# SCH-HC15C_REV1_PG3.net
KiCad netlist of a schematic drawn in Altium Designer
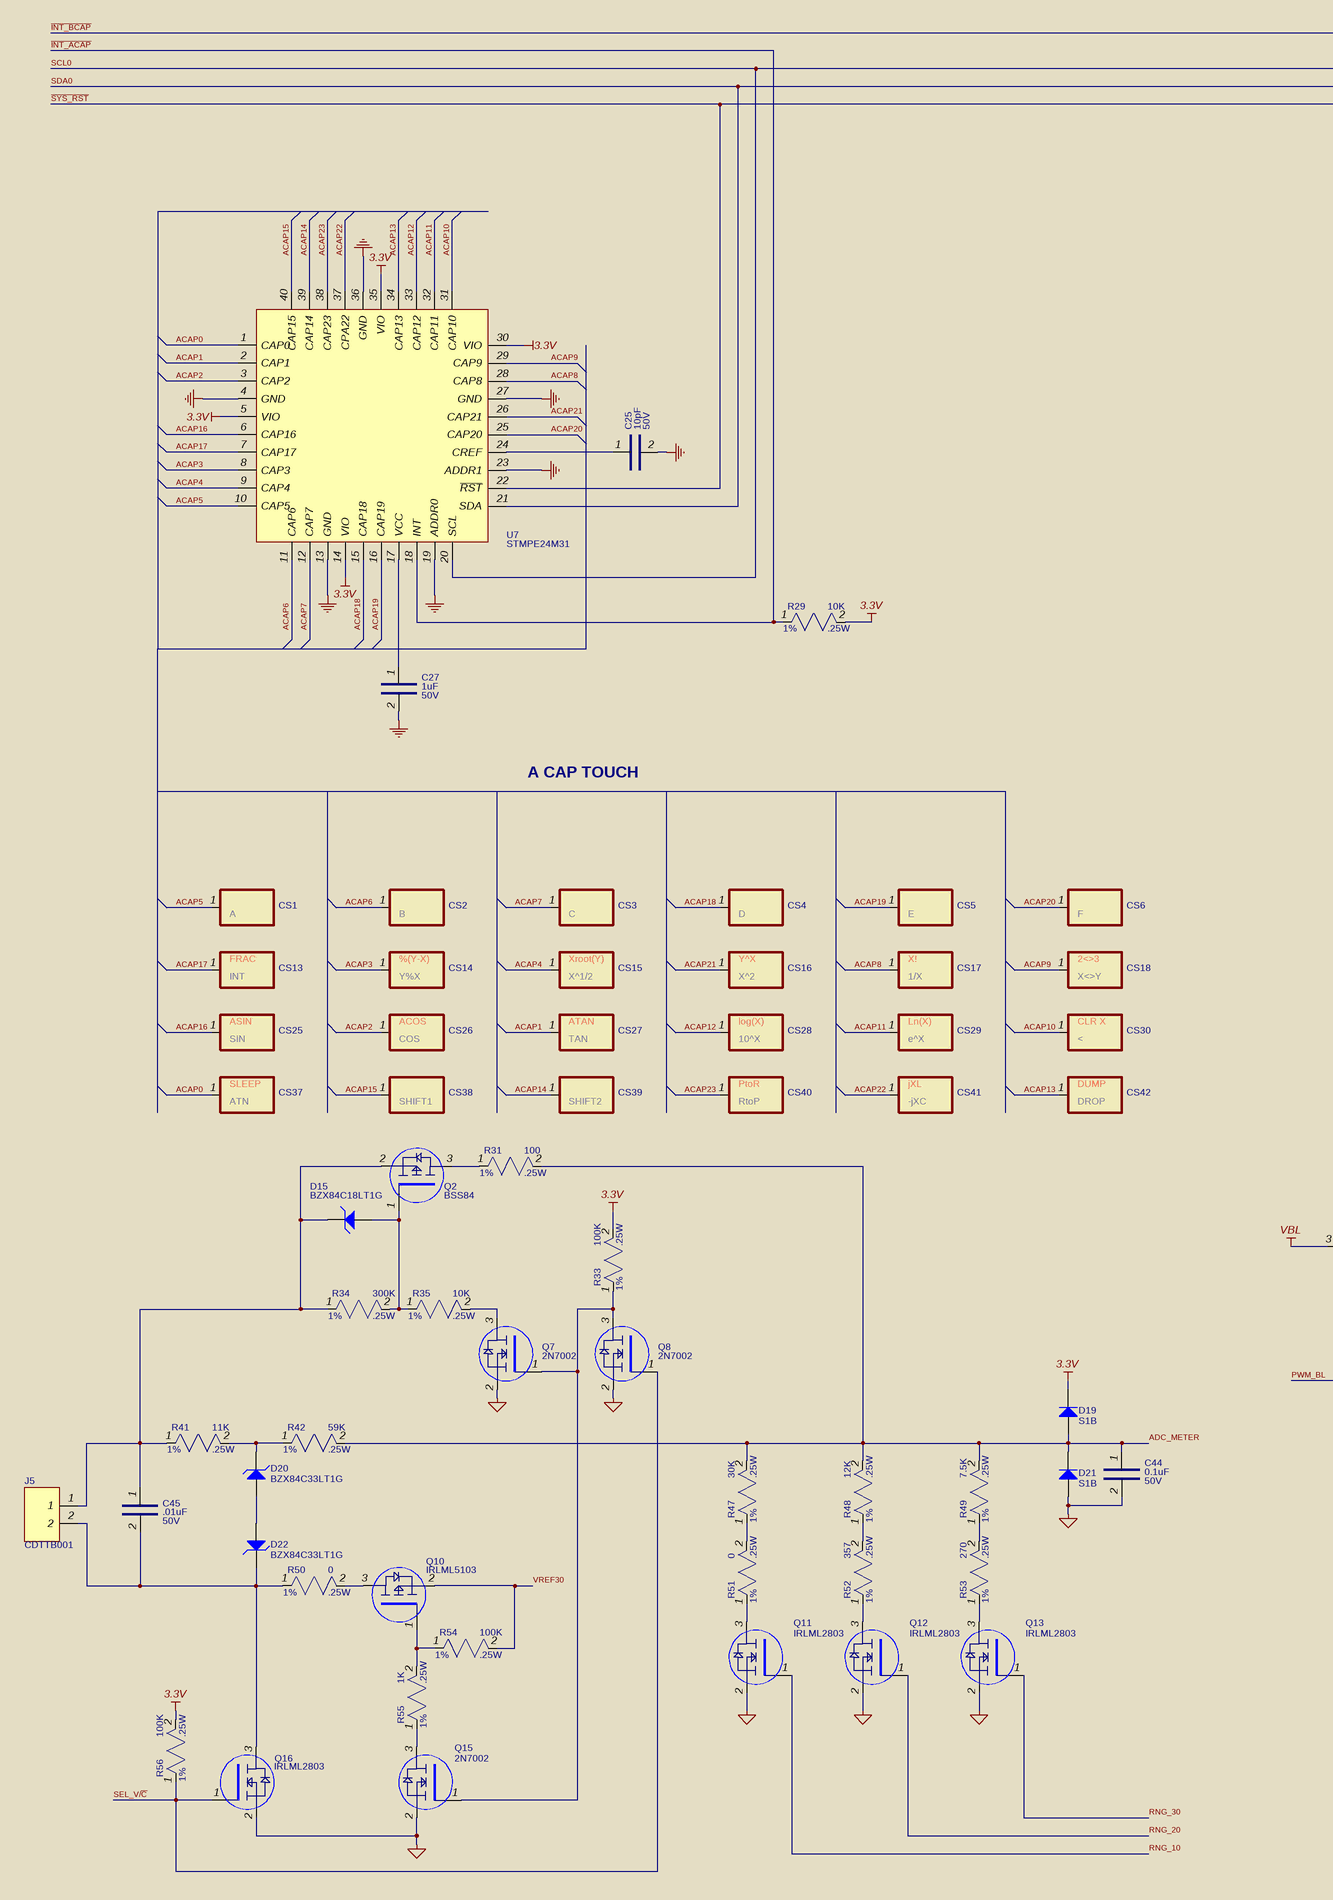
[diagram p0: SCH-HC15C_REV1_PG3.SchDoc, left]
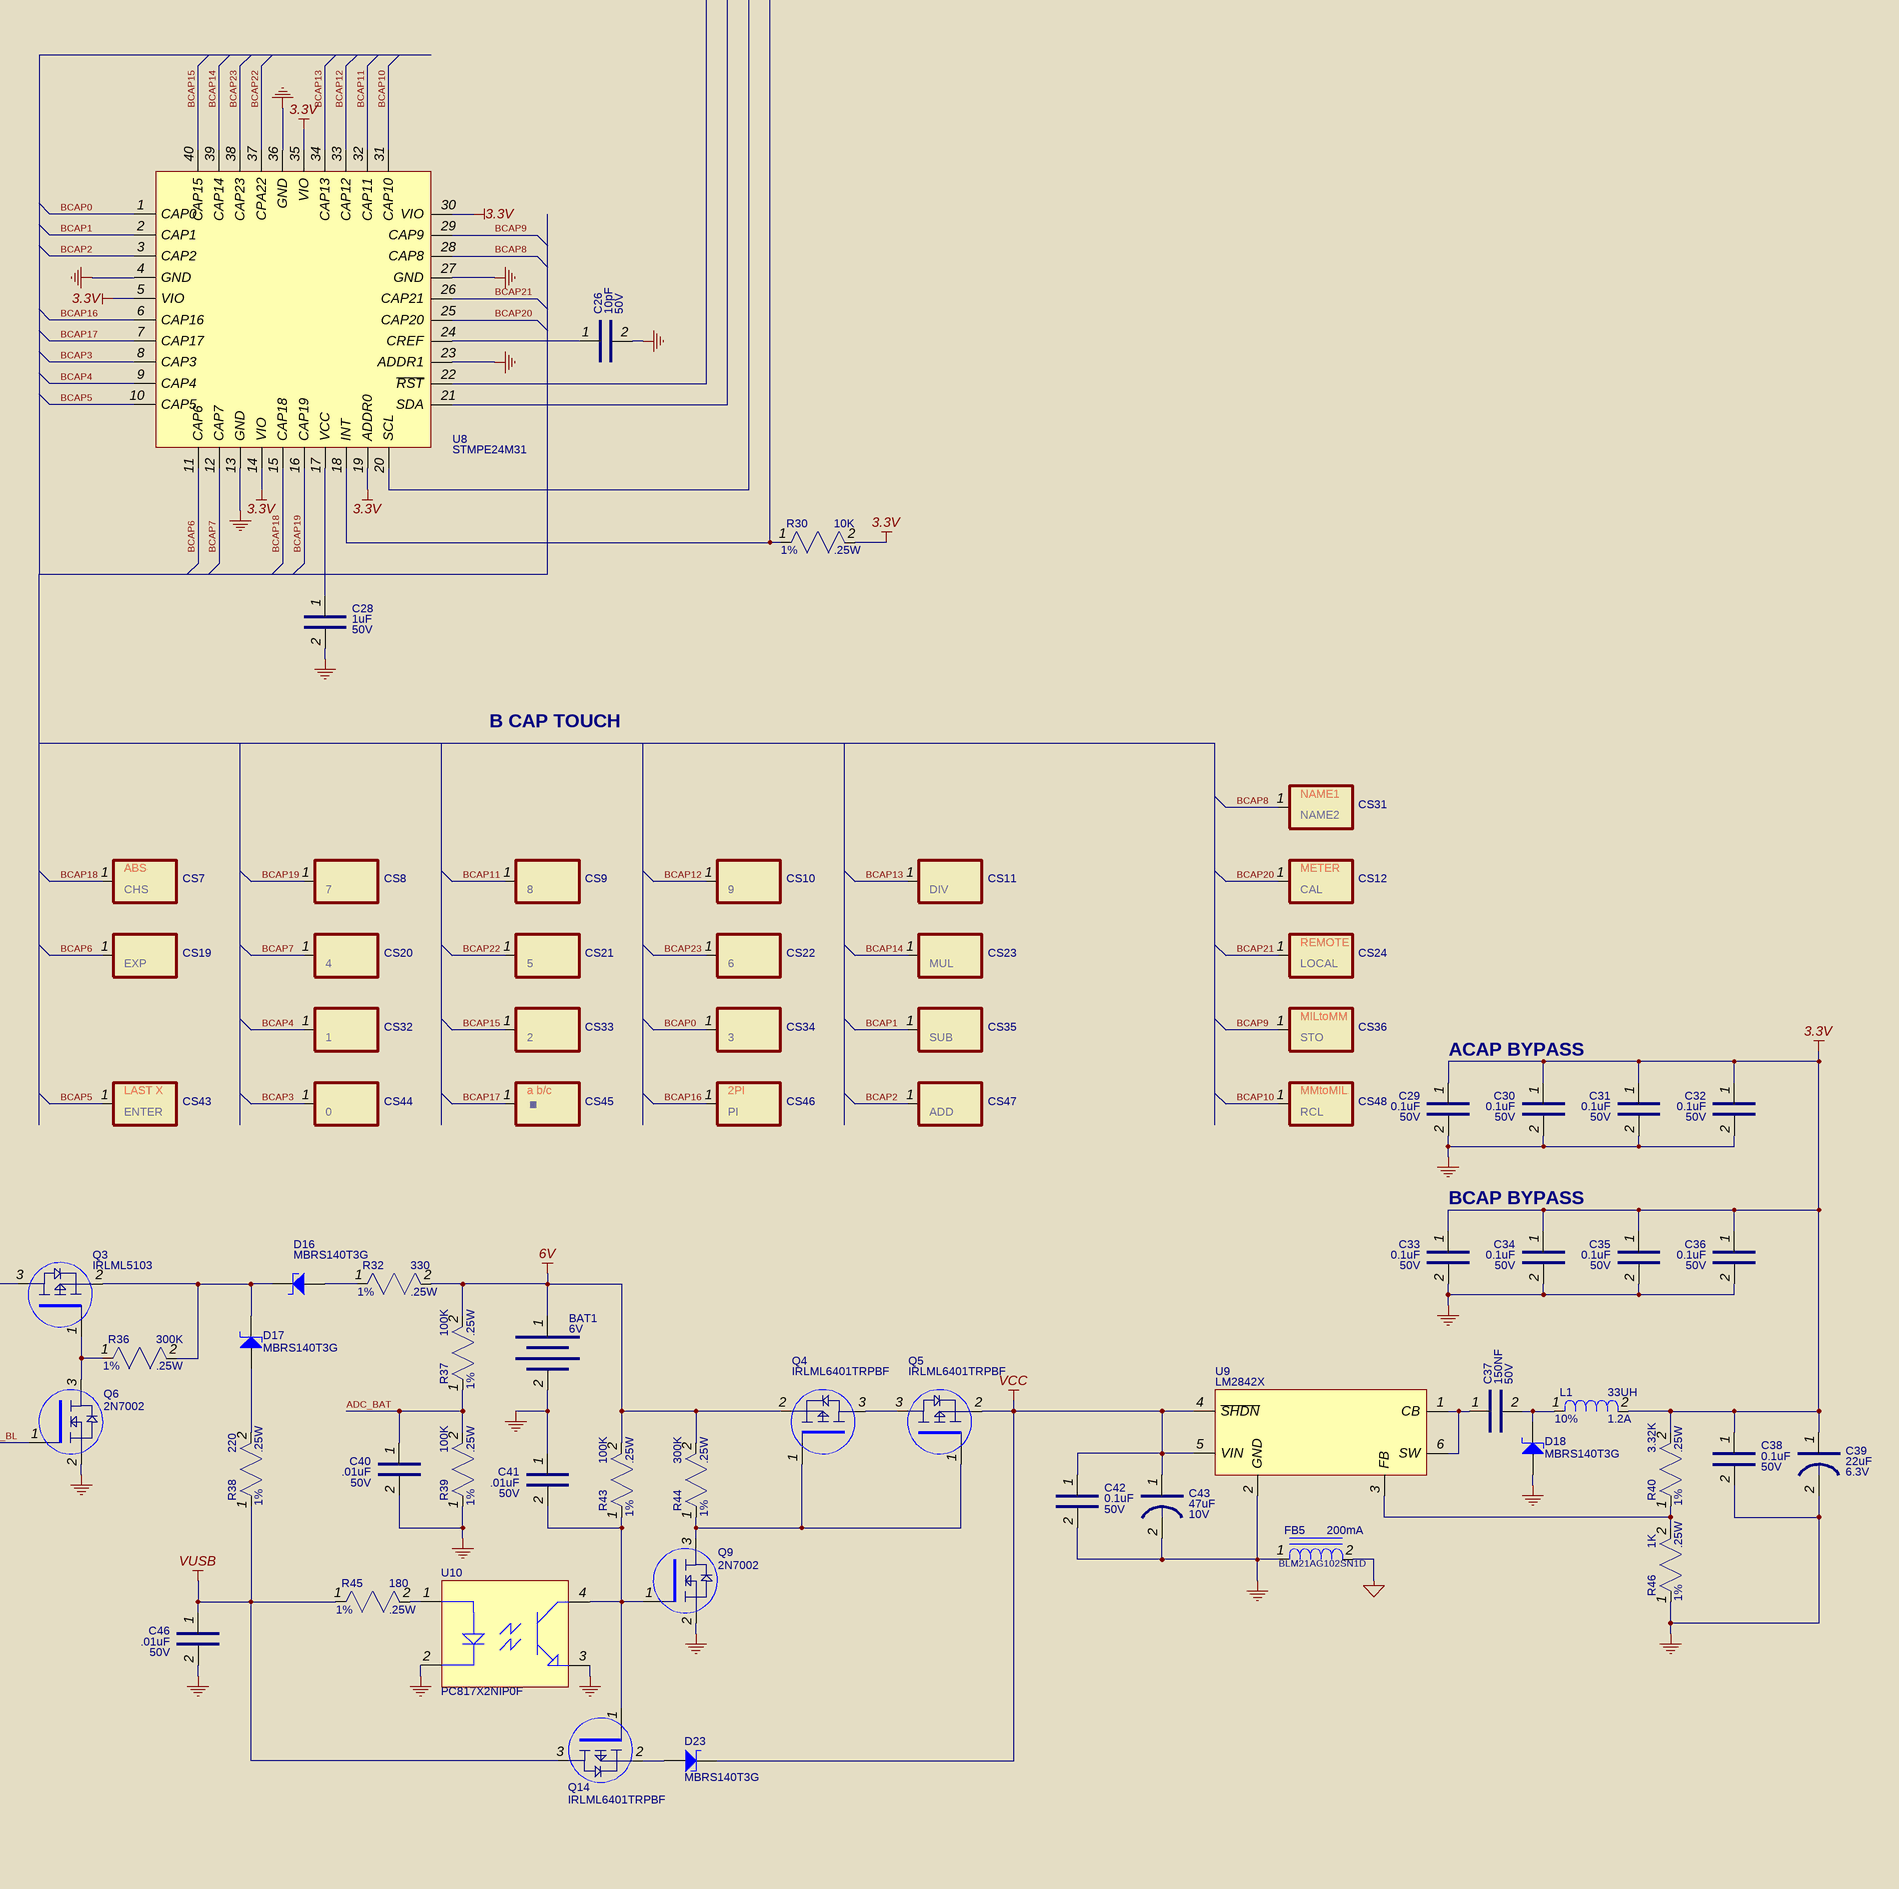
[diagram p1: SCH-HC15C_REV1_PG3.SchDoc, right]

(export (version "E")
  (design (tool "Eeschema 10.0.6"))
  (components
    (comp (ref "BAT1")
      (value "CDEVA00082_1")
      (footprint "KEYSTONE_1062")
      (description "CONN, BAT HOLDER 2-COIN CELL 20MM, SMD, ROHS")
      (fields (field (name "MFG") "KEYSTONE ELECTRONICS") (field (name "VOLTAGE") "6V"))
      (libsource (lib "HabLib") (part "CDEVA00082_1"))
    )
    (comp (ref "C25")
      (value "10pF")
      (footprint "3216[1206] - TAN COLOR")
      (description "CAP, CERAMIC, NPO, 10PF, 50V, 1206, 5%, RoHS")
      (fields (field (name "MFG") "AVX") (field (name "TOLERANCE") "10%") (field (name "VOLTAGE") "50V"))
      (libsource (lib "HabLib") (part "CDECA00143"))
    )
    (comp (ref "C26")
      (value "10pF")
      (footprint "3216[1206] - TAN COLOR")
      (description "CAP, CERAMIC, NPO, 10PF, 50V, 1206, 5%, RoHS")
      (fields (field (name "MFG") "AVX") (field (name "TOLERANCE") "10%") (field (name "VOLTAGE") "50V"))
      (libsource (lib "HabLib") (part "CDECA00143"))
    )
    (comp (ref "C27")
      (value "1uF")
      (footprint "3225[1210]")
      (description "CAP, CERAMIC CHIP 1UF 10% 50V X7R ROHS")
      (fields (field (name "MFG") "AVX") (field (name "TOLERANCE") "10%") (field (name "VOLTAGE") "50V"))
      (libsource (lib "HabLib") (part "CDECA00122"))
    )
    (comp (ref "C28")
      (value "1uF")
      (footprint "3225[1210]")
      (description "CAP, CERAMIC CHIP 1UF 10% 50V X7R ROHS")
      (fields (field (name "MFG") "AVX") (field (name "TOLERANCE") "10%") (field (name "VOLTAGE") "50V"))
      (libsource (lib "HabLib") (part "CDECA00122"))
    )
    (comp (ref "C29")
      (value "0.1uF")
      (footprint "3216[1206] - TAN COLOR")
      (description "CAP, CERAMIC CHIP 0.1UF 10% 50V X7R ROHS")
      (fields (field (name "MFG") "AVX") (field (name "TOLERANCE") "10%") (field (name "VOLTAGE") "50V"))
      (libsource (lib "HabLib") (part "CDECA00070"))
    )
    (comp (ref "C30")
      (value "0.1uF")
      (footprint "3216[1206] - TAN COLOR")
      (description "CAP, CERAMIC CHIP 0.1UF 10% 50V X7R ROHS")
      (fields (field (name "MFG") "AVX") (field (name "TOLERANCE") "10%") (field (name "VOLTAGE") "50V"))
      (libsource (lib "HabLib") (part "CDECA00070"))
    )
    (comp (ref "C31")
      (value "0.1uF")
      (footprint "3216[1206] - TAN COLOR")
      (description "CAP, CERAMIC CHIP 0.1UF 10% 50V X7R ROHS")
      (fields (field (name "MFG") "AVX") (field (name "TOLERANCE") "10%") (field (name "VOLTAGE") "50V"))
      (libsource (lib "HabLib") (part "CDECA00070"))
    )
    (comp (ref "C32")
      (value "0.1uF")
      (footprint "3216[1206] - TAN COLOR")
      (description "CAP, CERAMIC CHIP 0.1UF 10% 50V X7R ROHS")
      (fields (field (name "MFG") "AVX") (field (name "TOLERANCE") "10%") (field (name "VOLTAGE") "50V"))
      (libsource (lib "HabLib") (part "CDECA00070"))
    )
    (comp (ref "C33")
      (value "0.1uF")
      (footprint "3216[1206] - TAN COLOR")
      (description "CAP, CERAMIC CHIP 0.1UF 10% 50V X7R ROHS")
      (fields (field (name "MFG") "AVX") (field (name "TOLERANCE") "10%") (field (name "VOLTAGE") "50V"))
      (libsource (lib "HabLib") (part "CDECA00070"))
    )
    (comp (ref "C34")
      (value "0.1uF")
      (footprint "3216[1206] - TAN COLOR")
      (description "CAP, CERAMIC CHIP 0.1UF 10% 50V X7R ROHS")
      (fields (field (name "MFG") "AVX") (field (name "TOLERANCE") "10%") (field (name "VOLTAGE") "50V"))
      (libsource (lib "HabLib") (part "CDECA00070"))
    )
    (comp (ref "C35")
      (value "0.1uF")
      (footprint "3216[1206] - TAN COLOR")
      (description "CAP, CERAMIC CHIP 0.1UF 10% 50V X7R ROHS")
      (fields (field (name "MFG") "AVX") (field (name "TOLERANCE") "10%") (field (name "VOLTAGE") "50V"))
      (libsource (lib "HabLib") (part "CDECA00070"))
    )
    (comp (ref "C36")
      (value "0.1uF")
      (footprint "3216[1206] - TAN COLOR")
      (description "CAP, CERAMIC CHIP 0.1UF 10% 50V X7R ROHS")
      (fields (field (name "MFG") "AVX") (field (name "TOLERANCE") "10%") (field (name "VOLTAGE") "50V"))
      (libsource (lib "HabLib") (part "CDECA00070"))
    )
    (comp (ref "C37")
      (value "150NF")
      (footprint "3216[1206] - TAN COLOR")
      (description "CAP, CERAMIC, X7R, 150NF, 50V, 1206, 10%, RoHS")
      (fields (field (name "MFG") "KEMET") (field (name "TOLERANCE") "10%") (field (name "VOLTAGE") "50V"))
      (libsource (lib "HabLib") (part "CDECA00143_1"))
    )
    (comp (ref "C38")
      (value "0.1uF")
      (footprint "3216[1206] - TAN COLOR")
      (description "CAP, CERAMIC CHIP 0.1UF 10% 50V X7R ROHS")
      (fields (field (name "MFG") "AVX") (field (name "TOLERANCE") "10%") (field (name "VOLTAGE") "50V"))
      (libsource (lib "HabLib") (part "CDECA00070"))
    )
    (comp (ref "C39")
      (value "22uF")
      (footprint "3216[1206] - TANTALUM")
      (description "CAP, TANT, 22UF, 6.3V, 20%, LOW ESR, 1206ROHS")
      (fields (field (name "MFG") "AVX") (field (name "TOLERANCE") "20%") (field (name "VOLTAGE") "6.3V"))
      (libsource (lib "HabLib") (part "CDECA00139_1"))
    )
    (comp (ref "C40")
      (value ".01uF")
      (footprint "3216[1206] - TAN COLOR")
      (description "CAP, CERAMIC CHIP 0.01UF 10% 50V X7R ROHS")
      (fields
        (field (name "MFG") "PANASONIC")
        (field (name "TOLERANCE") "10%")
        (field (name "VOLTAGE") "50V")
      )
      (libsource (lib "") (part "CDECA00085_1"))
    )
    (comp (ref "C41")
      (value ".01uF")
      (footprint "3216[1206] - TAN COLOR")
      (description "CAP, CERAMIC CHIP 0.01UF 10% 50V X7R ROHS")
      (fields
        (field (name "MFG") "PANASONIC")
        (field (name "TOLERANCE") "10%")
        (field (name "VOLTAGE") "50V")
      )
      (libsource (lib "") (part "CDECA00085_1"))
    )
    (comp (ref "C42")
      (value "0.1uF")
      (footprint "3216[1206] - TAN COLOR")
      (description "CAP, CERAMIC CHIP 0.1UF 10% 50V X7R ROHS")
      (fields (field (name "MFG") "AVX") (field (name "TOLERANCE") "10%") (field (name "VOLTAGE") "50V"))
      (libsource (lib "HabLib") (part "CDECA00070"))
    )
    (comp (ref "C43")
      (value "47uF")
      (footprint "CAP_TANT_3528")
      (description "CAP, TANT, 47UF, 25V, 20%, 3528 ROHS")
      (fields (field (name "MFG") "AVX") (field (name "TOLERANCE") "20%") (field (name "VOLTAGE") "10V"))
      (libsource (lib "HabLib") (part "CDECA00110_1"))
    )
    (comp (ref "C44")
      (value "0.1uF")
      (footprint "3216[1206] - TAN COLOR")
      (description "CAP, CERAMIC CHIP 0.1UF 10% 50V X7R ROHS")
      (fields (field (name "MFG") "AVX") (field (name "TOLERANCE") "10%") (field (name "VOLTAGE") "50V"))
      (libsource (lib "HabLib") (part "CDECA00070"))
    )
    (comp (ref "C45")
      (value ".01uF")
      (footprint "3216[1206] - TAN COLOR")
      (description "CAP, CERAMIC CHIP 0.01UF 10% 50V X7R ROHS")
      (fields
        (field (name "MFG") "PANASONIC")
        (field (name "TOLERANCE") "10%")
        (field (name "VOLTAGE") "50V")
      )
      (libsource (lib "HabLib") (part "CDECA00085"))
    )
    (comp (ref "C46")
      (value ".01uF")
      (footprint "3216[1206] - TAN COLOR")
      (description "CAP, CERAMIC CHIP 0.01UF 10% 50V X7R ROHS")
      (fields
        (field (name "MFG") "PANASONIC")
        (field (name "TOLERANCE") "10%")
        (field (name "VOLTAGE") "50V")
      )
      (libsource (lib "") (part "CDECA00085_1"))
    )
    (comp (ref "CS1")
      (value "CAP_SENSOR")
      (footprint "CAPTOUCH1_10X10")
      (description "CAP SENSOR FOR PCB")
      (fields (field (name "VALUE2") "A") (field (name "PUBLISHER") "Altium Limited"))
      (libsource (lib "HabLib") (part "CAP_SENSOR"))
    )
    (comp (ref "CS2")
      (value "CAP_SENSOR")
      (footprint "CAPTOUCH1_10X10")
      (description "CAP SENSOR FOR PCB")
      (fields (field (name "VALUE2") "B") (field (name "PUBLISHER") "Altium Limited"))
      (libsource (lib "HabLib") (part "CAP_SENSOR"))
    )
    (comp (ref "CS3")
      (value "CAP_SENSOR")
      (footprint "CAPTOUCH1_10X10")
      (description "CAP SENSOR FOR PCB")
      (fields (field (name "VALUE2") "C") (field (name "PUBLISHER") "Altium Limited"))
      (libsource (lib "HabLib") (part "CAP_SENSOR"))
    )
    (comp (ref "CS4")
      (value "CAP_SENSOR")
      (footprint "CAPTOUCH1_10X10")
      (description "CAP SENSOR FOR PCB")
      (fields (field (name "VALUE2") "D") (field (name "PUBLISHER") "Altium Limited"))
      (libsource (lib "HabLib") (part "CAP_SENSOR"))
    )
    (comp (ref "CS5")
      (value "CAP_SENSOR")
      (footprint "CAPTOUCH1_10X10")
      (description "CAP SENSOR FOR PCB")
      (fields (field (name "VALUE2") "E") (field (name "PUBLISHER") "Altium Limited"))
      (libsource (lib "HabLib") (part "CAP_SENSOR"))
    )
    (comp (ref "CS6")
      (value "CAP_SENSOR")
      (footprint "CAPTOUCH1_10X10")
      (description "CAP SENSOR FOR PCB")
      (fields (field (name "VALUE2") "F") (field (name "PUBLISHER") "Altium Limited"))
      (libsource (lib "HabLib") (part "CAP_SENSOR"))
    )
    (comp (ref "CS7")
      (value "ABS")
      (footprint "CAPTOUCH1_10X10")
      (description "CAP SENSOR FOR PCB")
      (fields
        (field (name "VALUE2") "CHS")
        (field (name "Comment") "CAP_SENSOR")
        (field (name "PUBLISHER") "Altium Limited")
      )
      (libsource (lib "HabLib") (part "CAP_SENSOR"))
    )
    (comp (ref "CS8")
      (value "CAP_SENSOR")
      (footprint "CAPTOUCH1_10X10")
      (description "CAP SENSOR FOR PCB")
      (fields (field (name "VALUE2") "7") (field (name "PUBLISHER") "Altium Limited"))
      (libsource (lib "HabLib") (part "CAP_SENSOR"))
    )
    (comp (ref "CS9")
      (value "CAP_SENSOR")
      (footprint "CAPTOUCH1_10X10")
      (description "CAP SENSOR FOR PCB")
      (fields (field (name "VALUE2") "8") (field (name "PUBLISHER") "Altium Limited"))
      (libsource (lib "HabLib") (part "CAP_SENSOR"))
    )
    (comp (ref "CS10")
      (value "CAP_SENSOR")
      (footprint "CAPTOUCH1_10X10")
      (description "CAP SENSOR FOR PCB")
      (fields (field (name "VALUE2") "9") (field (name "PUBLISHER") "Altium Limited"))
      (libsource (lib "HabLib") (part "CAP_SENSOR"))
    )
    (comp (ref "CS11")
      (value "CAP_SENSOR")
      (footprint "CAPTOUCH1_10X10")
      (description "CAP SENSOR FOR PCB")
      (fields (field (name "VALUE2") "DIV") (field (name "PUBLISHER") "Altium Limited"))
      (libsource (lib "HabLib") (part "CAP_SENSOR"))
    )
    (comp (ref "CS12")
      (value "METER")
      (footprint "CAPTOUCH1_10X10")
      (description "CAP SENSOR FOR PCB")
      (fields
        (field (name "VALUE2") "CAL")
        (field (name "Comment") "CAP_SENSOR")
        (field (name "PUBLISHER") "Altium Limited")
      )
      (libsource (lib "HabLib") (part "CAP_SENSOR"))
    )
    (comp (ref "CS13")
      (value "FRAC")
      (footprint "CAPTOUCH1_10X10")
      (description "CAP SENSOR FOR PCB")
      (fields
        (field (name "VALUE2") "INT")
        (field (name "Comment") "CAP_SENSOR")
        (field (name "PUBLISHER") "Altium Limited")
      )
      (libsource (lib "HabLib") (part "CAP_SENSOR"))
    )
    (comp (ref "CS14")
      (value "%(Y-X)")
      (footprint "CAPTOUCH1_10X10")
      (description "CAP SENSOR FOR PCB")
      (fields
        (field (name "VALUE2") "Y%X")
        (field (name "Comment") "CAP_SENSOR")
        (field (name "PUBLISHER") "Altium Limited")
      )
      (libsource (lib "HabLib") (part "CAP_SENSOR"))
    )
    (comp (ref "CS15")
      (value "Xroot(Y)")
      (footprint "CAPTOUCH1_10X10")
      (description "CAP SENSOR FOR PCB")
      (fields
        (field (name "VALUE2") "X^1/2")
        (field (name "Comment") "CAP_SENSOR")
        (field (name "PUBLISHER") "Altium Limited")
      )
      (libsource (lib "HabLib") (part "CAP_SENSOR"))
    )
    (comp (ref "CS16")
      (value "Y^X")
      (footprint "CAPTOUCH1_10X10")
      (description "CAP SENSOR FOR PCB")
      (fields
        (field (name "VALUE2") "X^2")
        (field (name "Comment") "CAP_SENSOR")
        (field (name "PUBLISHER") "Altium Limited")
      )
      (libsource (lib "HabLib") (part "CAP_SENSOR"))
    )
    (comp (ref "CS17")
      (value "X!")
      (footprint "CAPTOUCH1_10X10")
      (description "CAP SENSOR FOR PCB")
      (fields
        (field (name "VALUE2") "1/X")
        (field (name "Comment") "CAP_SENSOR")
        (field (name "PUBLISHER") "Altium Limited")
      )
      (libsource (lib "HabLib") (part "CAP_SENSOR"))
    )
    (comp (ref "CS18")
      (value "2<>3")
      (footprint "CAPTOUCH1_10X10")
      (description "CAP SENSOR FOR PCB")
      (fields
        (field (name "VALUE2") "X<>Y")
        (field (name "Comment") "CAP_SENSOR")
        (field (name "PUBLISHER") "Altium Limited")
      )
      (libsource (lib "HabLib") (part "CAP_SENSOR"))
    )
    (comp (ref "CS19")
      (value "CAP_SENSOR")
      (footprint "CAPTOUCH1_10X10")
      (description "CAP SENSOR FOR PCB")
      (fields (field (name "VALUE2") "EXP") (field (name "PUBLISHER") "Altium Limited"))
      (libsource (lib "HabLib") (part "CAP_SENSOR"))
    )
    (comp (ref "CS20")
      (value "CAP_SENSOR")
      (footprint "CAPTOUCH1_10X10")
      (description "CAP SENSOR FOR PCB")
      (fields (field (name "VALUE2") "4") (field (name "PUBLISHER") "Altium Limited"))
      (libsource (lib "HabLib") (part "CAP_SENSOR"))
    )
    (comp (ref "CS21")
      (value "CAP_SENSOR")
      (footprint "CAPTOUCH1_10X10")
      (description "CAP SENSOR FOR PCB")
      (fields (field (name "VALUE2") "5") (field (name "PUBLISHER") "Altium Limited"))
      (libsource (lib "HabLib") (part "CAP_SENSOR"))
    )
    (comp (ref "CS22")
      (value "CAP_SENSOR")
      (footprint "CAPTOUCH1_10X10")
      (description "CAP SENSOR FOR PCB")
      (fields (field (name "VALUE2") "6") (field (name "PUBLISHER") "Altium Limited"))
      (libsource (lib "HabLib") (part "CAP_SENSOR"))
    )
    (comp (ref "CS23")
      (value "CAP_SENSOR")
      (footprint "CAPTOUCH1_10X10")
      (description "CAP SENSOR FOR PCB")
      (fields (field (name "VALUE2") "MUL") (field (name "PUBLISHER") "Altium Limited"))
      (libsource (lib "HabLib") (part "CAP_SENSOR"))
    )
    (comp (ref "CS24")
      (value "REMOTE")
      (footprint "CAPTOUCH1_10X10")
      (description "CAP SENSOR FOR PCB")
      (fields
        (field (name "VALUE2") "LOCAL")
        (field (name "Comment") "CAP_SENSOR")
        (field (name "PUBLISHER") "Altium Limited")
      )
      (libsource (lib "HabLib") (part "CAP_SENSOR"))
    )
    (comp (ref "CS25")
      (value "ASIN")
      (footprint "CAPTOUCH1_10X10")
      (description "CAP SENSOR FOR PCB")
      (fields
        (field (name "VALUE2") "SIN")
        (field (name "Comment") "CAP_SENSOR")
        (field (name "PUBLISHER") "Altium Limited")
      )
      (libsource (lib "HabLib") (part "CAP_SENSOR"))
    )
    (comp (ref "CS26")
      (value "ACOS")
      (footprint "CAPTOUCH1_10X10")
      (description "CAP SENSOR FOR PCB")
      (fields
        (field (name "VALUE2") "COS")
        (field (name "Comment") "CAP_SENSOR")
        (field (name "PUBLISHER") "Altium Limited")
      )
      (libsource (lib "HabLib") (part "CAP_SENSOR"))
    )
    (comp (ref "CS27")
      (value "ATAN")
      (footprint "CAPTOUCH1_10X10")
      (description "CAP SENSOR FOR PCB")
      (fields
        (field (name "VALUE2") "TAN")
        (field (name "Comment") "CAP_SENSOR")
        (field (name "PUBLISHER") "Altium Limited")
      )
      (libsource (lib "HabLib") (part "CAP_SENSOR"))
    )
    (comp (ref "CS28")
      (value "log(X)")
      (footprint "CAPTOUCH1_10X10")
      (description "CAP SENSOR FOR PCB")
      (fields
        (field (name "VALUE2") "10^X")
        (field (name "Comment") "CAP_SENSOR")
        (field (name "PUBLISHER") "Altium Limited")
      )
      (libsource (lib "HabLib") (part "CAP_SENSOR"))
    )
    (comp (ref "CS29")
      (value "Ln(X)")
      (footprint "CAPTOUCH1_10X10")
      (description "CAP SENSOR FOR PCB")
      (fields
        (field (name "VALUE2") "e^X")
        (field (name "Comment") "CAP_SENSOR")
        (field (name "PUBLISHER") "Altium Limited")
      )
      (libsource (lib "HabLib") (part "CAP_SENSOR"))
    )
    (comp (ref "CS30")
      (value "CLR X")
      (footprint "CAPTOUCH1_10X10")
      (description "CAP SENSOR FOR PCB")
      (fields
        (field (name "VALUE2") "<")
        (field (name "Comment") "CAP_SENSOR")
        (field (name "PUBLISHER") "Altium Limited")
      )
      (libsource (lib "HabLib") (part "CAP_SENSOR"))
    )
    (comp (ref "CS31")
      (value "NAME1")
      (footprint "CAPTOUCH1_10X10")
      (description "CAP SENSOR FOR PCB")
      (fields
        (field (name "VALUE2") "NAME2")
        (field (name "Comment") "CAP_SENSOR")
        (field (name "PUBLISHER") "Altium Limited")
      )
      (libsource (lib "HabLib") (part "CAP_SENSOR"))
    )
    (comp (ref "CS32")
      (value "CAP_SENSOR")
      (footprint "CAPTOUCH1_10X10")
      (description "CAP SENSOR FOR PCB")
      (fields (field (name "VALUE2") "1") (field (name "PUBLISHER") "Altium Limited"))
      (libsource (lib "HabLib") (part "CAP_SENSOR"))
    )
    (comp (ref "CS33")
      (value "CAP_SENSOR")
      (footprint "CAPTOUCH1_10X10")
      (description "CAP SENSOR FOR PCB")
      (fields (field (name "VALUE2") "2") (field (name "PUBLISHER") "Altium Limited"))
      (libsource (lib "HabLib") (part "CAP_SENSOR"))
    )
    (comp (ref "CS34")
      (value "CAP_SENSOR")
      (footprint "CAPTOUCH1_10X10")
      (description "CAP SENSOR FOR PCB")
      (fields (field (name "VALUE2") "3") (field (name "PUBLISHER") "Altium Limited"))
      (libsource (lib "HabLib") (part "CAP_SENSOR"))
    )
    (comp (ref "CS35")
      (value "CAP_SENSOR")
      (footprint "CAPTOUCH1_10X10")
      (description "CAP SENSOR FOR PCB")
      (fields (field (name "VALUE2") "SUB") (field (name "PUBLISHER") "Altium Limited"))
      (libsource (lib "HabLib") (part "CAP_SENSOR"))
    )
    (comp (ref "CS36")
      (value "MILtoMM")
      (footprint "CAPTOUCH1_10X10")
      (description "CAP SENSOR FOR PCB")
      (fields
        (field (name "VALUE2") "STO")
        (field (name "Comment") "CAP_SENSOR")
        (field (name "PUBLISHER") "Altium Limited")
      )
      (libsource (lib "HabLib") (part "CAP_SENSOR"))
    )
    (comp (ref "CS37")
      (value "SLEEP")
      (footprint "CAPTOUCH1_10X10")
      (description "CAP SENSOR FOR PCB")
      (fields
        (field (name "VALUE2") "ATN")
        (field (name "Comment") "CAP_SENSOR")
        (field (name "PUBLISHER") "Altium Limited")
      )
      (libsource (lib "HabLib") (part "CAP_SENSOR"))
    )
    (comp (ref "CS38")
      (value "CAP_SENSOR")
      (footprint "CAPTOUCH1_10X10")
      (description "CAP SENSOR FOR PCB")
      (fields (field (name "VALUE2") "SHIFT1") (field (name "PUBLISHER") "Altium Limited"))
      (libsource (lib "HabLib") (part "CAP_SENSOR"))
    )
    (comp (ref "CS39")
      (value "CAP_SENSOR")
      (footprint "CAPTOUCH1_10X10")
      (description "CAP SENSOR FOR PCB")
      (fields (field (name "VALUE2") "SHIFT2") (field (name "PUBLISHER") "Altium Limited"))
      (libsource (lib "HabLib") (part "CAP_SENSOR"))
    )
    (comp (ref "CS40")
      (value "PtoR")
      (footprint "CAPTOUCH1_10X10")
      (description "CAP SENSOR FOR PCB")
      (fields
        (field (name "VALUE2") "RtoP")
        (field (name "Comment") "CAP_SENSOR")
        (field (name "PUBLISHER") "Altium Limited")
      )
      (libsource (lib "HabLib") (part "CAP_SENSOR"))
    )
    (comp (ref "CS41")
      (value "jXL")
      (footprint "CAPTOUCH1_10X10")
      (description "CAP SENSOR FOR PCB")
      (fields
        (field (name "VALUE2") "-jXC")
        (field (name "Comment") "CAP_SENSOR")
        (field (name "PUBLISHER") "Altium Limited")
      )
      (libsource (lib "HabLib") (part "CAP_SENSOR"))
    )
    (comp (ref "CS42")
      (value "DUMP")
      (footprint "CAPTOUCH1_10X10")
      (description "CAP SENSOR FOR PCB")
      (fields
        (field (name "VALUE2") "DROP")
        (field (name "Comment") "CAP_SENSOR")
        (field (name "PUBLISHER") "Altium Limited")
      )
      (libsource (lib "HabLib") (part "CAP_SENSOR"))
    )
    (comp (ref "CS43")
      (value "LAST X")
      (footprint "CAPTOUCH1_10X23")
      (description "CAP SENSOR FOR PCB")
      (fields
        (field (name "VALUE2") "ENTER")
        (field (name "Comment") "CAP_SENSOR_ENT")
        (field (name "PUBLISHER") "Altium Limited")
      )
      (libsource (lib "HabLib") (part "CAP_SENSOR_ENT"))
    )
    (comp (ref "CS44")
      (value "CAP_SENSOR")
      (footprint "CAPTOUCH1_10X10")
      (description "CAP SENSOR FOR PCB")
      (fields (field (name "VALUE2") "0") (field (name "PUBLISHER") "Altium Limited"))
      (libsource (lib "HabLib") (part "CAP_SENSOR"))
    )
    (comp (ref "CS45")
      (value "a b/c")
      (footprint "CAPTOUCH1_10X10")
      (description "CAP SENSOR FOR PCB")
      (fields
        (field (name "VALUE2") ".")
        (field (name "Comment") "CAP_SENSOR")
        (field (name "PUBLISHER") "Altium Limited")
      )
      (libsource (lib "HabLib") (part "CAP_SENSOR"))
    )
    (comp (ref "CS46")
      (value "2PI")
      (footprint "CAPTOUCH1_10X10")
      (description "CAP SENSOR FOR PCB")
      (fields
        (field (name "VALUE2") "PI")
        (field (name "Comment") "CAP_SENSOR")
        (field (name "PUBLISHER") "Altium Limited")
      )
      (libsource (lib "HabLib") (part "CAP_SENSOR"))
    )
    (comp (ref "CS47")
      (value "CAP_SENSOR")
      (footprint "CAPTOUCH1_10X10")
      (description "CAP SENSOR FOR PCB")
      (fields (field (name "VALUE2") "ADD") (field (name "PUBLISHER") "Altium Limited"))
      (libsource (lib "HabLib") (part "CAP_SENSOR"))
    )
    (comp (ref "CS48")
      (value "MMtoMIL")
      (footprint "CAPTOUCH1_10X10")
      (description "CAP SENSOR FOR PCB")
      (fields
        (field (name "VALUE2") "RCL")
        (field (name "Comment") "CAP_SENSOR")
        (field (name "PUBLISHER") "Altium Limited")
      )
      (libsource (lib "HabLib") (part "CAP_SENSOR"))
    )
    (comp (ref "D15")
      (value "BZX84C18LT1G")
      (footprint "SOT23 - TRANSISTOR")
      (description "DIODE, ZENER, 18V, 225MW, SOT-23, ROHS")
      (fields (field (name "MFG") "ON SEMICONDUCTOR") (field (name "Comment") "CDEDA00055_1"))
      (libsource (lib "HabLib") (part "CDEDA00055_1"))
    )
    (comp (ref "D16")
      (value "MBRS140T3G")
      (footprint "DIODE_SMB")
      (description "Diode, Schottky rectifier, 40V, 1A, SMB package, Pb free")
      (fields
        (field (name "MFG") "ON SEMICONDUCTOR")
        (field (name "Comment") "CDEDA00019")
        (field (name "PUBLISHER") "Altium Limited")
      )
      (libsource (lib "HabLib") (part "CDEDA00019"))
    )
    (comp (ref "D17")
      (value "MBRS140T3G")
      (footprint "DIODE_SMB")
      (description "Diode, Schottky rectifier, 40V, 1A, SMB package, Pb free")
      (fields
        (field (name "MFG") "ON SEMICONDUCTOR")
        (field (name "Comment") "CDEDA00019")
        (field (name "PUBLISHER") "Altium Limited")
      )
      (libsource (lib "HabLib") (part "CDEDA00019"))
    )
    (comp (ref "D18")
      (value "MBRS140T3G")
      (footprint "DIODE_SMB")
      (description "Diode, Schottky rectifier, 40V, 1A, SMB package, Pb free")
      (fields
        (field (name "MFG") "ON SEMICONDUCTOR")
        (field (name "Comment") "CDEDA00019")
        (field (name "PUBLISHER") "Altium Limited")
      )
      (libsource (lib "HabLib") (part "CDEDA00019"))
    )
    (comp (ref "D19")
      (value "S1B")
      (footprint "DIODE SMA")
      (description "DIODE, 1A, 100V, SMA, ROHS")
      (fields (field (name "MFG") "FAIRCHILD SEMICONDUCTOR") (field (name "Comment") "CDEDA00055_3"))
      (libsource (lib "HabLib") (part "CDEDA00055_3"))
    )
    (comp (ref "D20")
      (value "BZX84C33LT1G")
      (footprint "SOT23 - TRANSISTOR")
      (description "DIODE, ZENER, 33V, 225MW, SOT-23, ROHS")
      (fields (field (name "MFG") "ON SEMICONDUCTOR") (field (name "Comment") "CDEDA00055_2"))
      (libsource (lib "HabLib") (part "CDEDA00055_2"))
    )
    (comp (ref "D21")
      (value "S1B")
      (footprint "DIODE SMA")
      (description "DIODE, 1A, 100V, SMA, ROHS")
      (fields (field (name "MFG") "FAIRCHILD SEMICONDUCTOR") (field (name "Comment") "CDEDA00055_3"))
      (libsource (lib "HabLib") (part "CDEDA00055_3"))
    )
    (comp (ref "D22")
      (value "BZX84C33LT1G")
      (footprint "SOT23 - TRANSISTOR")
      (description "DIODE, ZENER, 33V, 225MW, SOT-23, ROHS")
      (fields (field (name "MFG") "ON SEMICONDUCTOR") (field (name "Comment") "CDEDA00055_2"))
      (libsource (lib "HabLib") (part "CDEDA00055_2"))
    )
    (comp (ref "D23")
      (value "MBRS140T3G")
      (footprint "DIODE_SMB")
      (description "Diode, Schottky rectifier, 40V, 1A, SMB package, Pb free")
      (fields
        (field (name "MFG") "ON SEMICONDUCTOR")
        (field (name "Comment") "CDEDA00019")
        (field (name "PUBLISHER") "Altium Limited")
      )
      (libsource (lib "HabLib") (part "CDEDA00019"))
    )
    (comp (ref "FB5")
      (value "CDEVA00115")
      (footprint "2012[0805]")
      (description "FERRITE, 1KOHM AT 100MHZ, 220MA, .450DCR")
      (fields
        (field (name "MFG") "MURATA")
        (field (name "TOLERANCE") "10%")
        (field (name "MFG_PN") "BLM21AG102SN1D")
        (field (name "POWER") "200mA")
        (field (name "PUBLISHER") "Altium Limited")
      )
      (libsource (lib "HabLib") (part "CDEVA00115"))
    )
    (comp (ref "J5")
      (value "CDTTB001")
      (footprint "PHOENIX_CONTACT_1933189")
      (description "CONN, HDR, 2PIN, 5MM PHONIX CONTACT, ROHS")
      (fields (field (name "MFG") "PHOENIX CONTACT"))
      (libsource (lib "HabLib") (part "CDTTB001"))
    )
    (comp (ref "L1")
      (value "33UH")
      (footprint "BOURNS_SDR0805-XXXX")
      (description "INDUCTOR, 33UH, 10%, SMT, NON-SHIELDED, FERRITE CORE, ROHS")
      (fields
        (field (name "MFG") "BOURNS")
        (field (name "TOLERANCE") "10%")
        (field (name "POWER") "1.2A")
        (field (name "Comment") "CDEHA00005_1")
      )
      (libsource (lib "HabLib") (part "CDEHA00005_1"))
    )
    (comp (ref "Q2")
      (value "BSS84")
      (footprint "SOT23 - TRANSISTOR")
      (description "MOSFET P CHN, VDS=50V, RDSON = 10OHM, SOT 23")
      (fields
        (field (name "MFG") "DIODES INC")
        (field (name "Comment") "CDENA00031_1")
        (field (name "PUBLISHER") "Altium Limited")
      )
      (libsource (lib "HabLib") (part "CDENA00031_1"))
    )
    (comp (ref "Q3")
      (value "IRLML5103")
      (footprint "SOT23 - TRANSISTOR")
      (description "MOSFET P CHN, VDS=30V, RDSON = .6OHM, SOT 23")
      (fields
        (field (name "MFG") "INTERNATIONAL RECTIFIER")
        (field (name "Comment") "CDENA00031")
        (field (name "PUBLISHER") "Altium Limited")
      )
      (libsource (lib "HabLib") (part "CDENA00031"))
    )
    (comp (ref "Q4")
      (value "IRLML6401TRPBF")
      (footprint "SOT23 - TRANSISTOR")
      (description "MOSFET P CHN, VDS=12V, RDSON = .05OHM, SOT 23")
      (fields
        (field (name "MFG") "INTERNATIONAL RECTIFIER")
        (field (name "Comment") "CDENA00031_3")
        (field (name "PUBLISHER") "Altium Limited")
      )
      (libsource (lib "HabLib") (part "CDENA00031_3"))
    )
    (comp (ref "Q5")
      (value "IRLML6401TRPBF")
      (footprint "SOT23 - TRANSISTOR")
      (description "MOSFET P CHN, VDS=12V, RDSON = .05OHM, SOT 23")
      (fields
        (field (name "MFG") "INTERNATIONAL RECTIFIER")
        (field (name "Comment") "CDENA00031_3")
        (field (name "PUBLISHER") "Altium Limited")
      )
      (libsource (lib "") (part "CDENA00031_3_1"))
    )
    (comp (ref "Q6")
      (value "2N7002")
      (footprint "SOT23 - TRANSISTOR")
      (description "MOSFET N CHN, VDS=60V, 115 mA, SOT 23")
      (fields
        (field (name "MFG") "DIODES INC")
        (field (name "Comment") "CDENA00030")
        (field (name "PUBLISHER") "Altium Limited")
      )
      (libsource (lib "") (part "CDENA00030_1"))
    )
    (comp (ref "Q7")
      (value "2N7002")
      (footprint "SOT23 - TRANSISTOR")
      (description "MOSFET N CHN, VDS=60V, 115 mA, SOT 23")
      (fields
        (field (name "MFG") "DIODES INC")
        (field (name "Comment") "CDENA00030")
        (field (name "PUBLISHER") "Altium Limited")
      )
      (libsource (lib "HabLib") (part "CDENA00030"))
    )
    (comp (ref "Q8")
      (value "2N7002")
      (footprint "SOT23 - TRANSISTOR")
      (description "MOSFET N CHN, VDS=60V, 115 mA, SOT 23")
      (fields
        (field (name "MFG") "DIODES INC")
        (field (name "Comment") "CDENA00030")
        (field (name "PUBLISHER") "Altium Limited")
      )
      (libsource (lib "HabLib") (part "CDENA00030"))
    )
    (comp (ref "Q9")
      (value "2N7002")
      (footprint "SOT23 - TRANSISTOR")
      (description "MOSFET N CHN, VDS=60V, 115 mA, SOT 23")
      (fields
        (field (name "MFG") "DIODES INC")
        (field (name "Comment") "CDENA00030")
        (field (name "PUBLISHER") "Altium Limited")
      )
      (libsource (lib "") (part "CDENA00030_1"))
    )
    (comp (ref "Q10")
      (value "IRLML5103")
      (footprint "SOT23 - TRANSISTOR")
      (description "MOSFET P CHN, VDS=30V, RDSON = .6OHM, SOT 23")
      (fields
        (field (name "MFG") "INTERNATIONAL RECTIFIER")
        (field (name "Comment") "CDENA00031")
        (field (name "PUBLISHER") "Altium Limited")
      )
      (libsource (lib "HabLib") (part "CDENA00031"))
    )
    (comp (ref "Q11")
      (value "IRLML2803")
      (footprint "SOT23 - TRANSISTOR")
      (description "MOSFET N CHN, VDS=60V, 115 mA, SOT 23")
      (fields
        (field (name "MFG") "INTERNATIONAL RECTIFIER")
        (field (name "Comment") "CDENA00031_2")
        (field (name "PUBLISHER") "Altium Limited")
      )
      (libsource (lib "HabLib") (part "CDENA00031_2"))
    )
    (comp (ref "Q12")
      (value "IRLML2803")
      (footprint "SOT23 - TRANSISTOR")
      (description "MOSFET N CHN, VDS=60V, 115 mA, SOT 23")
      (fields
        (field (name "MFG") "INTERNATIONAL RECTIFIER")
        (field (name "Comment") "CDENA00031_2")
        (field (name "PUBLISHER") "Altium Limited")
      )
      (libsource (lib "HabLib") (part "CDENA00031_2"))
    )
    (comp (ref "Q13")
      (value "IRLML2803")
      (footprint "SOT23 - TRANSISTOR")
      (description "MOSFET N CHN, VDS=60V, 115 mA, SOT 23")
      (fields
        (field (name "MFG") "INTERNATIONAL RECTIFIER")
        (field (name "Comment") "CDENA00031_2")
        (field (name "PUBLISHER") "Altium Limited")
      )
      (libsource (lib "HabLib") (part "CDENA00031_2"))
    )
    (comp (ref "Q14")
      (value "IRLML6401TRPBF")
      (footprint "SOT23 - TRANSISTOR")
      (description "MOSFET P CHN, VDS=12V, RDSON = .05OHM, SOT 23")
      (fields
        (field (name "MFG") "INTERNATIONAL RECTIFIER")
        (field (name "Comment") "CDENA00031_3")
        (field (name "PUBLISHER") "Altium Limited")
      )
      (libsource (lib "HabLib") (part "CDENA00031_3"))
    )
    (comp (ref "Q15")
      (value "2N7002")
      (footprint "SOT23 - TRANSISTOR")
      (description "MOSFET N CHN, VDS=60V, 115 mA, SOT 23")
      (fields
        (field (name "MFG") "DIODES INC")
        (field (name "Comment") "CDENA00030")
        (field (name "PUBLISHER") "Altium Limited")
      )
      (libsource (lib "HabLib") (part "CDENA00030"))
    )
    (comp (ref "Q16")
      (value "IRLML2803")
      (footprint "SOT23 - TRANSISTOR")
      (description "MOSFET N CHN, VDS=60V, 115 mA, SOT 23")
      (fields
        (field (name "MFG") "INTERNATIONAL RECTIFIER")
        (field (name "Comment") "CDENA00031_2")
        (field (name "PUBLISHER") "Altium Limited")
      )
      (libsource (lib "") (part "CDENA00031_2_1"))
    )
    (comp (ref "R29")
      (value "10K")
      (footprint "HabLib:3216[1206]")
      (description "RESISTOR, CHIP 1206 10K OHM 1% 1/4W THICK FILM ROHS")
      (fields
        (field (name "MFG") "PANASONIC")
        (field (name "TOLERANCE") "1%")
        (field (name "POWER") ".25W")
        (field (name "Comment") "CDERA00170")
        (field (name "PUBLISHER") "Altium Limited")
      )
      (libsource (lib "HabLib") (part "CDERA00170"))
    )
    (comp (ref "R30")
      (value "10K")
      (footprint "HabLib:3216[1206]")
      (description "RESISTOR, CHIP 1206 10K OHM 1% 1/4W THICK FILM ROHS")
      (fields
        (field (name "MFG") "PANASONIC")
        (field (name "TOLERANCE") "1%")
        (field (name "POWER") ".25W")
        (field (name "Comment") "CDERA00170")
        (field (name "PUBLISHER") "Altium Limited")
      )
      (libsource (lib "HabLib") (part "CDERA00170"))
    )
    (comp (ref "R31")
      (value "100")
      (footprint "HabLib:3216[1206]")
      (description "RESISTOR, CHIP 1206 100 OHM 1% 1/4W THICK FILM ROHS")
      (fields
        (field (name "MFG") "PANASONIC")
        (field (name "TOLERANCE") "1%")
        (field (name "POWER") ".25W")
        (field (name "Comment") "CDERA00176")
        (field (name "PUBLISHER") "Altium Limited")
      )
      (libsource (lib "HabLib") (part "CDERA00176"))
    )
    (comp (ref "R32")
      (value "330")
      (footprint "HABLIB:3216[1206]")
      (description "RESISTOR, CHIP 1206 330 OHM 1% 1/4W THICK FILM ROHS")
      (fields
        (field (name "MFG") "PANASONIC")
        (field (name "TOLERANCE") "1%")
        (field (name "POWER") ".25W")
        (field (name "Comment") "CDERA00154")
        (field (name "PUBLISHER") "Altium Limited")
      )
      (libsource (lib "HabLib") (part "CDERA00154"))
    )
    (comp (ref "R33")
      (value "100K")
      (footprint "HABLIB:3216[1206]")
      (description "RESISTOR, CHIP 1206 100K OHM 1% 1/4W THICK FILM ROHS")
      (fields
        (field (name "MFG") "PANASONIC")
        (field (name "TOLERANCE") "1%")
        (field (name "POWER") ".25W")
        (field (name "Comment") "CDERA00198")
        (field (name "PUBLISHER") "Altium Limited")
      )
      (libsource (lib "HabLib") (part "CDERA00198"))
    )
    (comp (ref "R34")
      (value "300K")
      (footprint "HABLIB:3216[1206]")
      (description "RESISTOR, CHIP 1206 300K OHM 1% 1/4W THICK FILM ROHS")
      (fields
        (field (name "MFG") "PANASONIC")
        (field (name "TOLERANCE") "1%")
        (field (name "POWER") ".25W")
        (field (name "Comment") "CDERA00275_8")
        (field (name "PUBLISHER") "Altium Limited")
      )
      (libsource (lib "HabLib") (part "CDERA00275_8"))
    )
    (comp (ref "R35")
      (value "10K")
      (footprint "HabLib:3216[1206]")
      (description "RESISTOR, CHIP 1206 10K OHM 1% 1/4W THICK FILM ROHS")
      (fields
        (field (name "MFG") "PANASONIC")
        (field (name "TOLERANCE") "1%")
        (field (name "POWER") ".25W")
        (field (name "Comment") "CDERA00170")
        (field (name "PUBLISHER") "Altium Limited")
      )
      (libsource (lib "HabLib") (part "CDERA00170"))
    )
    (comp (ref "R36")
      (value "300K")
      (footprint "HABLIB:3216[1206]")
      (description "RESISTOR, CHIP 1206 300K OHM 1% 1/4W THICK FILM ROHS")
      (fields
        (field (name "MFG") "PANASONIC")
        (field (name "TOLERANCE") "1%")
        (field (name "POWER") ".25W")
        (field (name "Comment") "CDERA00275_8")
        (field (name "PUBLISHER") "Altium Limited")
      )
      (libsource (lib "HabLib") (part "CDERA00275_8"))
    )
    (comp (ref "R37")
      (value "100K")
      (footprint "HABLIB:3216[1206]")
      (description "RESISTOR, CHIP 1206 100K OHM 1% 1/4W THICK FILM ROHS")
      (fields
        (field (name "MFG") "PANASONIC")
        (field (name "TOLERANCE") "1%")
        (field (name "POWER") ".25W")
        (field (name "Comment") "CDERA00198")
        (field (name "PUBLISHER") "Altium Limited")
      )
      (libsource (lib "HabLib") (part "CDERA00198"))
    )
    (comp (ref "R38")
      (value "220")
      (footprint "HABLIB:3216[1206]")
      (description "RESISTOR, CHIP 1206 220 OHM 1% 1/4W THICK FILM ROHS")
      (fields
        (field (name "MFG") "PANASONIC")
        (field (name "TOLERANCE") "1%")
        (field (name "POWER") ".25W")
        (field (name "Comment") "CDERA00273_2")
        (field (name "PUBLISHER") "Altium Limited")
      )
      (libsource (lib "HabLib") (part "CDERA00273_2"))
    )
    (comp (ref "R39")
      (value "100K")
      (footprint "HABLIB:3216[1206]")
      (description "RESISTOR, CHIP 1206 100K OHM 1% 1/4W THICK FILM ROHS")
      (fields
        (field (name "MFG") "PANASONIC")
        (field (name "TOLERANCE") "1%")
        (field (name "POWER") ".25W")
        (field (name "Comment") "CDERA00198")
        (field (name "PUBLISHER") "Altium Limited")
      )
      (libsource (lib "HabLib") (part "CDERA00198"))
    )
    (comp (ref "R40")
      (value "3.32K")
      (footprint "HABLIB:3216[1206]")
      (description "RESISTOR, CHIP 1206 3.32K OHM 1% 1/4W THICK FILM ROHS")
      (fields
        (field (name "MFG") "PANASONIC")
        (field (name "TOLERANCE") "1%")
        (field (name "POWER") ".25W")
        (field (name "Comment") "CDERA00273_1")
        (field (name "PUBLISHER") "Altium Limited")
      )
      (libsource (lib "HabLib") (part "CDERA00273_1"))
    )
    (comp (ref "R41")
      (value "11K")
      (footprint "HABLIB:3216[1206]")
      (description "RESISTOR, CHIP 1206 11K OHM 1% 1/4W THICK FILM ROHS")
      (fields
        (field (name "MFG") "PANASONIC")
        (field (name "TOLERANCE") "1%")
        (field (name "POWER") ".25W")
        (field (name "Comment") "CDERA00275_2")
        (field (name "PUBLISHER") "Altium Limited")
      )
      (libsource (lib "HabLib") (part "CDERA00275_2"))
    )
    (comp (ref "R42")
      (value "59K")
      (footprint "HABLIB:3216[1206]")
      (description "RESISTOR, CHIP 1206 59K OHM 1% 1/4W THICK FILM ROHS")
      (fields
        (field (name "MFG") "PANASONIC")
        (field (name "TOLERANCE") "1%")
        (field (name "POWER") ".25W")
        (field (name "Comment") "CDERA00275_7")
        (field (name "PUBLISHER") "Altium Limited")
      )
      (libsource (lib "HabLib") (part "CDERA00275_7"))
    )
    (comp (ref "R43")
      (value "100K")
      (footprint "HABLIB:3216[1206]")
      (description "RESISTOR, CHIP 1206 100K OHM 1% 1/4W THICK FILM ROHS")
      (fields
        (field (name "MFG") "PANASONIC")
        (field (name "TOLERANCE") "1%")
        (field (name "POWER") ".25W")
        (field (name "Comment") "CDERA00198")
        (field (name "PUBLISHER") "Altium Limited")
      )
      (libsource (lib "HabLib") (part "CDERA00198"))
    )
    (comp (ref "R44")
      (value "300K")
      (footprint "HABLIB:3216[1206]")
      (description "RESISTOR, CHIP 1206 300K OHM 1% 1/4W THICK FILM ROHS")
      (fields
        (field (name "MFG") "PANASONIC")
        (field (name "TOLERANCE") "1%")
        (field (name "POWER") ".25W")
        (field (name "Comment") "CDERA00275_8")
        (field (name "PUBLISHER") "Altium Limited")
      )
      (libsource (lib "HabLib") (part "CDERA00275_8"))
    )
    (comp (ref "R45")
      (value "180")
      (footprint "HABLIB:3216[1206]")
      (description "RESISTOR, CHIP 1206 180 OHM 1% 1/4W THICK FILM ROHS")
      (fields
        (field (name "MFG") "PANASONIC")
        (field (name "TOLERANCE") "1%")
        (field (name "POWER") ".25W")
        (field (name "Comment") "CDERA00192")
        (field (name "PUBLISHER") "Altium Limited")
      )
      (libsource (lib "HabLib") (part "CDERA00192"))
    )
    (comp (ref "R46")
      (value "1K")
      (footprint "HABLIB:3216[1206]")
      (description "RESISTOR, CHIP 1206 1K OHM 1% 1/4W THICK FILM ROHS")
      (fields
        (field (name "MFG") "PANASONIC")
        (field (name "TOLERANCE") "1%")
        (field (name "POWER") ".25W")
        (field (name "Comment") "CDERA00195")
        (field (name "PUBLISHER") "Altium Limited")
      )
      (libsource (lib "HabLib") (part "CDERA00195"))
    )
    (comp (ref "R47")
      (value "30K")
      (footprint "HABLIB:3216[1206]")
      (description "RESISTOR, CHIP 1206 30K OHM 1% 1/4W THICK FILM ROHS")
      (fields
        (field (name "MFG") "PANASONIC")
        (field (name "TOLERANCE") "1%")
        (field (name "POWER") ".25W")
        (field (name "Comment") "CDERA00275_4")
        (field (name "PUBLISHER") "Altium Limited")
      )
      (libsource (lib "HabLib") (part "CDERA00275_4"))
    )
    (comp (ref "R48")
      (value "12K")
      (footprint "HABLIB:3216[1206]")
      (description "RESISTOR, CHIP 1206 12K OHM 1% 1/4W THICK FILM ROHS")
      (fields
        (field (name "MFG") "PANASONIC")
        (field (name "TOLERANCE") "1%")
        (field (name "POWER") ".25W")
        (field (name "Comment") "CDERA00275_5")
        (field (name "PUBLISHER") "Altium Limited")
      )
      (libsource (lib "HabLib") (part "CDERA00275_5"))
    )
    (comp (ref "R49")
      (value "7.5K")
      (footprint "HABLIB:3216[1206]")
      (description "RESISTOR, CHIP 1206 7.5K OHM 1% 1/4W THICK FILM ROHS")
      (fields
        (field (name "MFG") "PANASONIC")
        (field (name "TOLERANCE") "1%")
        (field (name "POWER") ".25W")
        (field (name "Comment") "CDERA00275_3")
        (field (name "PUBLISHER") "Altium Limited")
      )
      (libsource (lib "HabLib") (part "CDERA00275_3"))
    )
    (comp (ref "R50")
      (value "0")
      (footprint "HABLIB:3216[1206]")
      (description "RESISTOR, CHIP 1206 0.0 OHM 1% 1/4W THICK FILM ROHS")
      (fields
        (field (name "MFG") "PANASONIC")
        (field (name "TOLERANCE") "1%")
        (field (name "POWER") ".25W")
        (field (name "Comment") "CDERA00181")
        (field (name "PUBLISHER") "Altium Limited")
      )
      (libsource (lib "HabLib") (part "CDERA00181"))
    )
    (comp (ref "R51")
      (value "0")
      (footprint "HABLIB:3216[1206]")
      (description "RESISTOR, CHIP 1206 0.0 OHM 1% 1/4W THICK FILM ROHS")
      (fields
        (field (name "MFG") "PANASONIC")
        (field (name "TOLERANCE") "1%")
        (field (name "POWER") ".25W")
        (field (name "Comment") "CDERA00181")
        (field (name "PUBLISHER") "Altium Limited")
      )
      (libsource (lib "HabLib") (part "CDERA00181"))
    )
    (comp (ref "R52")
      (value "357")
      (footprint "HABLIB:3216[1206]")
      (description "RESISTOR, CHIP 1206 357 OHM 1% 1/4W THICK FILM ROHS")
      (fields
        (field (name "MFG") "PANASONIC")
        (field (name "TOLERANCE") "1%")
        (field (name "POWER") ".25W")
        (field (name "Comment") "CDERA00275_6")
        (field (name "PUBLISHER") "Altium Limited")
      )
      (libsource (lib "HabLib") (part "CDERA00275_6"))
    )
    (comp (ref "R53")
      (value "270")
      (footprint "HABLIB:3216[1206]")
      (description "RESISTOR, CHIP 1206 270 OHM 1% 1/4W THICK FILM ROHS")
      (fields
        (field (name "MFG") "PANASONIC")
        (field (name "TOLERANCE") "1%")
        (field (name "POWER") ".25W")
        (field (name "Comment") "CDERA00209")
        (field (name "PUBLISHER") "Altium Limited")
      )
      (libsource (lib "HabLib") (part "CDERA00209"))
    )
    (comp (ref "R54")
      (value "100K")
      (footprint "HABLIB:3216[1206]")
      (description "RESISTOR, CHIP 1206 100K OHM 1% 1/4W THICK FILM ROHS")
      (fields
        (field (name "MFG") "PANASONIC")
        (field (name "TOLERANCE") "1%")
        (field (name "POWER") ".25W")
        (field (name "Comment") "CDERA00198")
        (field (name "PUBLISHER") "Altium Limited")
      )
      (libsource (lib "HabLib") (part "CDERA00198"))
    )
    (comp (ref "R55")
      (value "1K")
      (footprint "HABLIB:3216[1206]")
      (description "RESISTOR, CHIP 1206 1K OHM 1% 1/4W THICK FILM ROHS")
      (fields
        (field (name "MFG") "PANASONIC")
        (field (name "TOLERANCE") "1%")
        (field (name "POWER") ".25W")
        (field (name "Comment") "CDERA00195")
        (field (name "PUBLISHER") "Altium Limited")
      )
      (libsource (lib "HabLib") (part "CDERA00195"))
    )
    (comp (ref "R56")
      (value "100K")
      (footprint "HABLIB:3216[1206]")
      (description "RESISTOR, CHIP 1206 100K OHM 1% 1/4W THICK FILM ROHS")
      (fields
        (field (name "MFG") "PANASONIC")
        (field (name "TOLERANCE") "1%")
        (field (name "POWER") ".25W")
        (field (name "Comment") "CDERA00198")
        (field (name "PUBLISHER") "Altium Limited")
      )
      (libsource (lib "HabLib") (part "CDERA00198"))
    )
    (comp (ref "U7")
      (value "STMPE24M31")
      (footprint "QFN40P500X500X80-41V_MODIFIED")
      (description "IC, TOUCHKEY CONTROLLER, 24CH, I2C, 40QFN")
      (fields
        (field (name "MFG") "ST")
        (field (name "Comment") "CDEUA00052_1")
        (field (name "PUBLISHER") "Altium Limited")
      )
      (libsource (lib "HabLib") (part "CDEUA00052_1"))
    )
    (comp (ref "U8")
      (value "STMPE24M31")
      (footprint "QFN40P500X500X80-41V_MODIFIED")
      (description "IC, TOUCHKEY CONTROLLER, 24CH, I2C, 40QFN")
      (fields
        (field (name "MFG") "ST")
        (field (name "Comment") "CDEUA00052_1")
        (field (name "PUBLISHER") "Altium Limited")
      )
      (libsource (lib "HabLib") (part "CDEUA00052_1"))
    )
    (comp (ref "U9")
      (value "LM2842X")
      (footprint "TSOT6")
      (description "IC, BUCK REGULATOR, 0.6A, TSOT23-6")
      (fields (field (name "MFG") "NATIONAL SEMICONDUCTOR") (field (name "Comment") "CDEUA00014_1"))
      (libsource (lib "HabLib") (part "CDEUA00014_1"))
    )
    (comp (ref "U10")
      (value "PC817X2NIP0F")
      (footprint "SHARP_PC817")
      (description "IC, PHOTOCOUPLER, NPN OUTPUT - NO BASE, SM, ROHS")
      (fields (field (name "MFG") "SHARP MICROELECTRONICS") (field (name "Comment") "CDEUA00013_1"))
      (libsource (lib "HabLib") (part "CDEUA00013_1"))
    )
  )
  (nets
    (net (code "1") (name "/ACAP0") (class "Default")
      (node (ref "CS37") (pin "1") (pinfunction "1_1") (pintype "passive"))
      (node (ref "U7") (pin "1") (pinfunction "CAP0_1") (pintype "passive"))
    )
    (net (code "2") (name "/ACAP1") (class "Default")
      (node (ref "CS27") (pin "1") (pinfunction "1_1") (pintype "passive"))
      (node (ref "U7") (pin "2") (pinfunction "CAP1_2") (pintype "passive"))
    )
    (net (code "3") (name "/ACAP2") (class "Default")
      (node (ref "CS26") (pin "1") (pinfunction "1_1") (pintype "passive"))
      (node (ref "U7") (pin "3") (pinfunction "CAP2_3") (pintype "passive"))
    )
    (net (code "4") (name "/ACAP3") (class "Default")
      (node (ref "CS14") (pin "1") (pinfunction "1_1") (pintype "passive"))
      (node (ref "U7") (pin "8") (pinfunction "CAP3_8") (pintype "passive"))
    )
    (net (code "5") (name "/ACAP4") (class "Default")
      (node (ref "CS15") (pin "1") (pinfunction "1_1") (pintype "passive"))
      (node (ref "U7") (pin "9") (pinfunction "CAP4_9") (pintype "passive"))
    )
    (net (code "6") (name "/ACAP5") (class "Default")
      (node (ref "CS1") (pin "1") (pinfunction "1_1") (pintype "passive"))
      (node (ref "U7") (pin "10") (pinfunction "CAP5_10") (pintype "passive"))
    )
    (net (code "7") (name "/ACAP6") (class "Default")
      (node (ref "CS2") (pin "1") (pinfunction "1_1") (pintype "passive"))
      (node (ref "U7") (pin "11") (pinfunction "CAP6_11") (pintype "passive"))
    )
    (net (code "8") (name "/ACAP7") (class "Default")
      (node (ref "CS3") (pin "1") (pinfunction "1_1") (pintype "passive"))
      (node (ref "U7") (pin "12") (pinfunction "CAP7_12") (pintype "passive"))
    )
    (net (code "9") (name "/ACAP8") (class "Default")
      (node (ref "CS17") (pin "1") (pinfunction "1_1") (pintype "passive"))
      (node (ref "U7") (pin "28") (pinfunction "CAP8_28") (pintype "passive"))
    )
    (net (code "10") (name "/ACAP9") (class "Default")
      (node (ref "CS18") (pin "1") (pinfunction "1_1") (pintype "passive"))
      (node (ref "U7") (pin "29") (pinfunction "CAP9_29") (pintype "passive"))
    )
    (net (code "11") (name "/ACAP10") (class "Default")
      (node (ref "CS30") (pin "1") (pinfunction "1_1") (pintype "passive"))
      (node (ref "U7") (pin "31") (pinfunction "CAP10_31") (pintype "passive"))
    )
    (net (code "12") (name "/ACAP11") (class "Default")
      (node (ref "CS29") (pin "1") (pinfunction "1_1") (pintype "passive"))
      (node (ref "U7") (pin "32") (pinfunction "CAP11_32") (pintype "passive"))
    )
    (net (code "13") (name "/ACAP12") (class "Default")
      (node (ref "CS28") (pin "1") (pinfunction "1_1") (pintype "passive"))
      (node (ref "U7") (pin "33") (pinfunction "CAP12_33") (pintype "passive"))
    )
    (net (code "14") (name "/ACAP13") (class "Default")
      (node (ref "CS42") (pin "1") (pinfunction "1_1") (pintype "passive"))
      (node (ref "U7") (pin "34") (pinfunction "CAP13_34") (pintype "passive"))
    )
    (net (code "15") (name "/ACAP14") (class "Default")
      (node (ref "CS39") (pin "1") (pinfunction "1_1") (pintype "passive"))
      (node (ref "U7") (pin "39") (pinfunction "CAP14_39") (pintype "passive"))
    )
    (net (code "16") (name "/ACAP15") (class "Default")
      (node (ref "CS38") (pin "1") (pinfunction "1_1") (pintype "passive"))
      (node (ref "U7") (pin "40") (pinfunction "CAP15_40") (pintype "passive"))
    )
    (net (code "17") (name "/ACAP16") (class "Default")
      (node (ref "CS25") (pin "1") (pinfunction "1_1") (pintype "passive"))
      (node (ref "U7") (pin "6") (pinfunction "CAP16_6") (pintype "passive"))
    )
    (net (code "18") (name "/ACAP17") (class "Default")
      (node (ref "CS13") (pin "1") (pinfunction "1_1") (pintype "passive"))
      (node (ref "U7") (pin "7") (pinfunction "CAP17_7") (pintype "passive"))
    )
    (net (code "19") (name "/ACAP18") (class "Default")
      (node (ref "CS4") (pin "1") (pinfunction "1_1") (pintype "passive"))
      (node (ref "U7") (pin "15") (pinfunction "CAP18_15") (pintype "passive"))
    )
    (net (code "20") (name "/ACAP19") (class "Default")
      (node (ref "CS5") (pin "1") (pinfunction "1_1") (pintype "passive"))
      (node (ref "U7") (pin "16") (pinfunction "CAP19_16") (pintype "passive"))
    )
    (net (code "21") (name "/ACAP20") (class "Default")
      (node (ref "CS6") (pin "1") (pinfunction "1_1") (pintype "passive"))
      (node (ref "U7") (pin "25") (pinfunction "CAP20_25") (pintype "passive"))
    )
    (net (code "22") (name "/ACAP21") (class "Default")
      (node (ref "CS16") (pin "1") (pinfunction "1_1") (pintype "passive"))
      (node (ref "U7") (pin "26") (pinfunction "CAP21_26") (pintype "passive"))
    )
    (net (code "23") (name "/ACAP22") (class "Default")
      (node (ref "CS41") (pin "1") (pinfunction "1_1") (pintype "passive"))
      (node (ref "U7") (pin "37") (pinfunction "CPA22_37") (pintype "passive"))
    )
    (net (code "24") (name "/ACAP23") (class "Default")
      (node (ref "CS40") (pin "1") (pinfunction "1_1") (pintype "passive"))
      (node (ref "U7") (pin "38") (pinfunction "CAP23_38") (pintype "passive"))
    )
    (net (code "25") (name "/ADC_BAT") (class "Default")
      (node (ref "C40") (pin "1") (pinfunction "1_1") (pintype "passive"))
      (node (ref "R37") (pin "1") (pinfunction "1_1") (pintype "passive"))
      (node (ref "R39") (pin "2") (pinfunction "2_2") (pintype "passive"))
    )
    (net (code "26") (name "/ADC_METER") (class "Default")
      (node (ref "C44") (pin "1") (pinfunction "1_1") (pintype "passive"))
      (node (ref "D19") (pin "1") (pinfunction "A_1") (pintype "passive"))
      (node (ref "D21") (pin "2") (pinfunction "K_2") (pintype "passive"))
      (node (ref "R31") (pin "2") (pinfunction "2_2") (pintype "passive"))
      (node (ref "R42") (pin "2") (pinfunction "2_2") (pintype "passive"))
      (node (ref "R47") (pin "2") (pinfunction "2_2") (pintype "passive"))
      (node (ref "R48") (pin "2") (pinfunction "2_2") (pintype "passive"))
      (node (ref "R49") (pin "2") (pinfunction "2_2") (pintype "passive"))
    )
    (net (code "27") (name "/BCAP0") (class "Default")
      (node (ref "CS34") (pin "1") (pinfunction "1_1") (pintype "passive"))
      (node (ref "U8") (pin "1") (pinfunction "CAP0_1") (pintype "passive"))
    )
    (net (code "28") (name "/BCAP1") (class "Default")
      (node (ref "CS35") (pin "1") (pinfunction "1_1") (pintype "passive"))
      (node (ref "U8") (pin "2") (pinfunction "CAP1_2") (pintype "passive"))
    )
    (net (code "29") (name "/BCAP2") (class "Default")
      (node (ref "CS47") (pin "1") (pinfunction "1_1") (pintype "passive"))
      (node (ref "U8") (pin "3") (pinfunction "CAP2_3") (pintype "passive"))
    )
    (net (code "30") (name "/BCAP3") (class "Default")
      (node (ref "CS44") (pin "1") (pinfunction "1_1") (pintype "passive"))
      (node (ref "U8") (pin "8") (pinfunction "CAP3_8") (pintype "passive"))
    )
    (net (code "31") (name "/BCAP4") (class "Default")
      (node (ref "CS32") (pin "1") (pinfunction "1_1") (pintype "passive"))
      (node (ref "U8") (pin "9") (pinfunction "CAP4_9") (pintype "passive"))
    )
    (net (code "32") (name "/BCAP5") (class "Default")
      (node (ref "CS43") (pin "1") (pinfunction "1_1") (pintype "passive"))
      (node (ref "U8") (pin "10") (pinfunction "CAP5_10") (pintype "passive"))
    )
    (net (code "33") (name "/BCAP6") (class "Default")
      (node (ref "CS19") (pin "1") (pinfunction "1_1") (pintype "passive"))
      (node (ref "U8") (pin "11") (pinfunction "CAP6_11") (pintype "passive"))
    )
    (net (code "34") (name "/BCAP7") (class "Default")
      (node (ref "CS20") (pin "1") (pinfunction "1_1") (pintype "passive"))
      (node (ref "U8") (pin "12") (pinfunction "CAP7_12") (pintype "passive"))
    )
    (net (code "35") (name "/BCAP8") (class "Default")
      (node (ref "CS31") (pin "1") (pinfunction "1_1") (pintype "passive"))
      (node (ref "U8") (pin "28") (pinfunction "CAP8_28") (pintype "passive"))
    )
    (net (code "36") (name "/BCAP9") (class "Default")
      (node (ref "CS36") (pin "1") (pinfunction "1_1") (pintype "passive"))
      (node (ref "U8") (pin "29") (pinfunction "CAP9_29") (pintype "passive"))
    )
    (net (code "37") (name "/BCAP10") (class "Default")
      (node (ref "CS48") (pin "1") (pinfunction "1_1") (pintype "passive"))
      (node (ref "U8") (pin "31") (pinfunction "CAP10_31") (pintype "passive"))
    )
    (net (code "38") (name "/BCAP11") (class "Default")
      (node (ref "CS9") (pin "1") (pinfunction "1_1") (pintype "passive"))
      (node (ref "U8") (pin "32") (pinfunction "CAP11_32") (pintype "passive"))
    )
    (net (code "39") (name "/BCAP12") (class "Default")
      (node (ref "CS10") (pin "1") (pinfunction "1_1") (pintype "passive"))
      (node (ref "U8") (pin "33") (pinfunction "CAP12_33") (pintype "passive"))
    )
    (net (code "40") (name "/BCAP13") (class "Default")
      (node (ref "CS11") (pin "1") (pinfunction "1_1") (pintype "passive"))
      (node (ref "U8") (pin "34") (pinfunction "CAP13_34") (pintype "passive"))
    )
    (net (code "41") (name "/BCAP14") (class "Default")
      (node (ref "CS23") (pin "1") (pinfunction "1_1") (pintype "passive"))
      (node (ref "U8") (pin "39") (pinfunction "CAP14_39") (pintype "passive"))
    )
    (net (code "42") (name "/BCAP15") (class "Default")
      (node (ref "CS33") (pin "1") (pinfunction "1_1") (pintype "passive"))
      (node (ref "U8") (pin "40") (pinfunction "CAP15_40") (pintype "passive"))
    )
    (net (code "43") (name "/BCAP16") (class "Default")
      (node (ref "CS46") (pin "1") (pinfunction "1_1") (pintype "passive"))
      (node (ref "U8") (pin "6") (pinfunction "CAP16_6") (pintype "passive"))
    )
    (net (code "44") (name "/BCAP17") (class "Default")
      (node (ref "CS45") (pin "1") (pinfunction "1_1") (pintype "passive"))
      (node (ref "U8") (pin "7") (pinfunction "CAP17_7") (pintype "passive"))
    )
    (net (code "45") (name "/BCAP18") (class "Default")
      (node (ref "CS7") (pin "1") (pinfunction "1_1") (pintype "passive"))
      (node (ref "U8") (pin "15") (pinfunction "CAP18_15") (pintype "passive"))
    )
    (net (code "46") (name "/BCAP19") (class "Default")
      (node (ref "CS8") (pin "1") (pinfunction "1_1") (pintype "passive"))
      (node (ref "U8") (pin "16") (pinfunction "CAP19_16") (pintype "passive"))
    )
    (net (code "47") (name "/BCAP20") (class "Default")
      (node (ref "CS12") (pin "1") (pinfunction "1_1") (pintype "passive"))
      (node (ref "U8") (pin "25") (pinfunction "CAP20_25") (pintype "passive"))
    )
    (net (code "48") (name "/BCAP21") (class "Default")
      (node (ref "CS24") (pin "1") (pinfunction "1_1") (pintype "passive"))
      (node (ref "U8") (pin "26") (pinfunction "CAP21_26") (pintype "passive"))
    )
    (net (code "49") (name "/BCAP22") (class "Default")
      (node (ref "CS21") (pin "1") (pinfunction "1_1") (pintype "passive"))
      (node (ref "U8") (pin "37") (pinfunction "CPA22_37") (pintype "passive"))
    )
    (net (code "50") (name "/BCAP23") (class "Default")
      (node (ref "CS22") (pin "1") (pinfunction "1_1") (pintype "passive"))
      (node (ref "U8") (pin "38") (pinfunction "CAP23_38") (pintype "passive"))
    )
    (net (code "51") (name "/INT_ACAP") (class "Default")
      (node (ref "R29") (pin "1") (pinfunction "1_1") (pintype "passive"))
      (node (ref "U7") (pin "18") (pinfunction "INT_18") (pintype "passive"))
    )
    (net (code "52") (name "/INT_BCAP") (class "Default")
      (node (ref "R30") (pin "1") (pinfunction "1_1") (pintype "passive"))
      (node (ref "U8") (pin "18") (pinfunction "INT_18") (pintype "passive"))
    )
    (net (code "53") (name "/PWM_BL") (class "Default")
      (node (ref "Q6") (pin "1") (pinfunction "B_1") (pintype "passive"))
    )
    (net (code "54") (name "/RNG_10") (class "Default")
      (node (ref "Q11") (pin "1") (pinfunction "B_1") (pintype "passive"))
    )
    (net (code "55") (name "/RNG_20") (class "Default")
      (node (ref "Q12") (pin "1") (pinfunction "B_1") (pintype "passive"))
    )
    (net (code "56") (name "/RNG_30") (class "Default")
      (node (ref "Q13") (pin "1") (pinfunction "B_1") (pintype "passive"))
    )
    (net (code "57") (name "/SCL0") (class "Default")
      (node (ref "U7") (pin "20") (pinfunction "SCL_20") (pintype "passive"))
      (node (ref "U8") (pin "20") (pinfunction "SCL_20") (pintype "passive"))
    )
    (net (code "58") (name "/SDA0") (class "Default")
      (node (ref "U7") (pin "21") (pinfunction "SDA_21") (pintype "passive"))
      (node (ref "U8") (pin "21") (pinfunction "SDA_21") (pintype "passive"))
    )
    (net (code "59") (name "/SEL_V{slash}~{C}") (class "Default")
      (node (ref "Q16") (pin "1") (pinfunction "B_1") (pintype "passive"))
      (node (ref "Q8") (pin "1") (pinfunction "B_1") (pintype "passive"))
      (node (ref "R56") (pin "1") (pinfunction "1_1") (pintype "passive"))
    )
    (net (code "60") (name "/SYS_RST") (class "Default")
      (node (ref "U7") (pin "22") (pinfunction "RST_22") (pintype "passive"))
      (node (ref "U8") (pin "22") (pinfunction "RST_22") (pintype "passive"))
    )
    (net (code "61") (name "/VREF30") (class "Default")
      (node (ref "Q10") (pin "2") (pinfunction "E_2") (pintype "passive"))
      (node (ref "R54") (pin "2") (pinfunction "2_2") (pintype "passive"))
    )
    (net (code "62") (name "3.3V") (class "Default")
      (node (ref "C29") (pin "1") (pinfunction "1_1") (pintype "passive"))
      (node (ref "C30") (pin "1") (pinfunction "1_1") (pintype "passive"))
      (node (ref "C31") (pin "1") (pinfunction "1_1") (pintype "passive"))
      (node (ref "C32") (pin "1") (pinfunction "1_1") (pintype "passive"))
      (node (ref "C33") (pin "1") (pinfunction "1_1") (pintype "passive"))
      (node (ref "C34") (pin "1") (pinfunction "1_1") (pintype "passive"))
      (node (ref "C35") (pin "1") (pinfunction "1_1") (pintype "passive"))
      (node (ref "C36") (pin "1") (pinfunction "1_1") (pintype "passive"))
      (node (ref "C38") (pin "1") (pinfunction "1_1") (pintype "passive"))
      (node (ref "C39") (pin "1") (pinfunction "1_1") (pintype "passive"))
      (node (ref "D19") (pin "2") (pinfunction "K_2") (pintype "passive"))
      (node (ref "L1") (pin "2") (pinfunction "2_2") (pintype "passive"))
      (node (ref "R29") (pin "2") (pinfunction "2_2") (pintype "passive"))
      (node (ref "R30") (pin "2") (pinfunction "2_2") (pintype "passive"))
      (node (ref "R33") (pin "2") (pinfunction "2_2") (pintype "passive"))
      (node (ref "R40") (pin "2") (pinfunction "2_2") (pintype "passive"))
      (node (ref "R56") (pin "2") (pinfunction "2_2") (pintype "passive"))
      (node (ref "U7") (pin "14") (pinfunction "VIO_14") (pintype "passive"))
      (node (ref "U7") (pin "30") (pinfunction "VIO_30") (pintype "passive"))
      (node (ref "U7") (pin "35") (pinfunction "VIO_35") (pintype "passive"))
      (node (ref "U7") (pin "5") (pinfunction "VIO_5") (pintype "passive"))
      (node (ref "U8") (pin "14") (pinfunction "VIO_14") (pintype "passive"))
      (node (ref "U8") (pin "19") (pinfunction "ADDR0_19") (pintype "passive"))
      (node (ref "U8") (pin "30") (pinfunction "VIO_30") (pintype "passive"))
      (node (ref "U8") (pin "35") (pinfunction "VIO_35") (pintype "passive"))
      (node (ref "U8") (pin "5") (pinfunction "VIO_5") (pintype "passive"))
    )
    (net (code "63") (name "6V") (class "Default")
      (node (ref "BAT1") (pin "1") (pinfunction "1_1") (pintype "passive"))
      (node (ref "Q4") (pin "2") (pinfunction "E_2") (pintype "passive"))
      (node (ref "R32") (pin "2") (pinfunction "2_2") (pintype "passive"))
      (node (ref "R37") (pin "2") (pinfunction "2_2") (pintype "passive"))
      (node (ref "R43") (pin "2") (pinfunction "2_2") (pintype "passive"))
      (node (ref "R44") (pin "2") (pinfunction "2_2") (pintype "passive"))
    )
    (net (code "64") (name "GND") (class "Default")
      (node (ref "BAT1") (pin "2") (pinfunction "2_2") (pintype "passive"))
      (node (ref "C25") (pin "2") (pinfunction "2_2") (pintype "passive"))
      (node (ref "C26") (pin "2") (pinfunction "2_2") (pintype "passive"))
      (node (ref "C27") (pin "2") (pinfunction "2_2") (pintype "passive"))
      (node (ref "C28") (pin "2") (pinfunction "2_2") (pintype "passive"))
      (node (ref "C29") (pin "2") (pinfunction "2_2") (pintype "passive"))
      (node (ref "C30") (pin "2") (pinfunction "2_2") (pintype "passive"))
      (node (ref "C31") (pin "2") (pinfunction "2_2") (pintype "passive"))
      (node (ref "C32") (pin "2") (pinfunction "2_2") (pintype "passive"))
      (node (ref "C33") (pin "2") (pinfunction "2_2") (pintype "passive"))
      (node (ref "C34") (pin "2") (pinfunction "2_2") (pintype "passive"))
      (node (ref "C35") (pin "2") (pinfunction "2_2") (pintype "passive"))
      (node (ref "C36") (pin "2") (pinfunction "2_2") (pintype "passive"))
      (node (ref "C38") (pin "2") (pinfunction "2_2") (pintype "passive"))
      (node (ref "C39") (pin "2") (pinfunction "2_2") (pintype "passive"))
      (node (ref "C40") (pin "2") (pinfunction "2_2") (pintype "passive"))
      (node (ref "C41") (pin "1") (pinfunction "1_1") (pintype "passive"))
      (node (ref "C42") (pin "2") (pinfunction "2_2") (pintype "passive"))
      (node (ref "C43") (pin "2") (pinfunction "2_2") (pintype "passive"))
      (node (ref "C46") (pin "2") (pinfunction "2_2") (pintype "passive"))
      (node (ref "D18") (pin "1") (pinfunction "A_1") (pintype "passive"))
      (node (ref "FB5") (pin "1") (pinfunction "1_1") (pintype "passive"))
      (node (ref "Q6") (pin "2") (pinfunction "E_2") (pintype "passive"))
      (node (ref "Q9") (pin "2") (pinfunction "E_2") (pintype "passive"))
      (node (ref "R39") (pin "1") (pinfunction "1_1") (pintype "passive"))
      (node (ref "R46") (pin "1") (pinfunction "1_1") (pintype "passive"))
      (node (ref "U10") (pin "2") (pintype "passive"))
      (node (ref "U10") (pin "3") (pintype "passive"))
      (node (ref "U7") (pin "13") (pinfunction "GND_13") (pintype "passive"))
      (node (ref "U7") (pin "19") (pinfunction "ADDR0_19") (pintype "passive"))
      (node (ref "U7") (pin "23") (pinfunction "ADDR1_23") (pintype "passive"))
      (node (ref "U7") (pin "27") (pinfunction "GND_27") (pintype "passive"))
      (node (ref "U7") (pin "36") (pinfunction "GND_36") (pintype "passive"))
      (node (ref "U7") (pin "4") (pinfunction "GND_4") (pintype "passive"))
      (node (ref "U8") (pin "13") (pinfunction "GND_13") (pintype "passive"))
      (node (ref "U8") (pin "23") (pinfunction "ADDR1_23") (pintype "passive"))
      (node (ref "U8") (pin "27") (pinfunction "GND_27") (pintype "passive"))
      (node (ref "U8") (pin "36") (pinfunction "GND_36") (pintype "passive"))
      (node (ref "U8") (pin "4") (pinfunction "GND_4") (pintype "passive"))
      (node (ref "U9") (pin "2") (pinfunction "GND_2") (pintype "passive"))
    )
    (net (code "65") (name "GNDA") (class "Default")
      (node (ref "C44") (pin "2") (pinfunction "2_2") (pintype "passive"))
      (node (ref "D21") (pin "1") (pinfunction "A_1") (pintype "passive"))
      (node (ref "FB5") (pin "2") (pinfunction "2_2") (pintype "passive"))
      (node (ref "Q11") (pin "2") (pinfunction "E_2") (pintype "passive"))
      (node (ref "Q12") (pin "2") (pinfunction "E_2") (pintype "passive"))
      (node (ref "Q13") (pin "2") (pinfunction "E_2") (pintype "passive"))
      (node (ref "Q15") (pin "2") (pinfunction "E_2") (pintype "passive"))
      (node (ref "Q16") (pin "2") (pinfunction "E_2") (pintype "passive"))
      (node (ref "Q7") (pin "2") (pinfunction "E_2") (pintype "passive"))
      (node (ref "Q8") (pin "2") (pinfunction "E_2") (pintype "passive"))
    )
    (net (code "66") (name "Net-(D15-A)") (class "Default")
      (node (ref "D15") (pin "1") (pinfunction "A_1") (pintype "passive"))
      (node (ref "Q2") (pin "1") (pinfunction "B_1") (pintype "passive"))
      (node (ref "R34") (pin "2") (pinfunction "2_2") (pintype "passive"))
      (node (ref "R35") (pin "1") (pinfunction "1_1") (pintype "passive"))
    )
    (net (code "67") (name "Net-(D15-K)") (class "Default")
      (node (ref "C45") (pin "1") (pinfunction "1_1") (pintype "passive"))
      (node (ref "D15") (pin "3") (pinfunction "K_3") (pintype "passive"))
      (node (ref "J5") (pin "1") (pinfunction "1_1") (pintype "passive"))
      (node (ref "Q2") (pin "2") (pinfunction "E_2") (pintype "passive"))
      (node (ref "R34") (pin "1") (pinfunction "1_1") (pintype "passive"))
      (node (ref "R41") (pin "1") (pinfunction "1_1") (pintype "passive"))
    )
    (net (code "68") (name "Net-(D16-A)") (class "Default")
      (node (ref "D16") (pin "1") (pinfunction "A_1") (pintype "passive"))
      (node (ref "R32") (pin "1") (pinfunction "1_1") (pintype "passive"))
    )
    (net (code "69") (name "Net-(D16-K)") (class "Default")
      (node (ref "D16") (pin "2") (pinfunction "K_2") (pintype "passive"))
      (node (ref "D17") (pin "2") (pinfunction "K_2") (pintype "passive"))
      (node (ref "Q3") (pin "2") (pinfunction "E_2") (pintype "passive"))
      (node (ref "R36") (pin "2") (pinfunction "2_2") (pintype "passive"))
    )
    (net (code "70") (name "Net-(D17-A)") (class "Default")
      (node (ref "D17") (pin "1") (pinfunction "A_1") (pintype "passive"))
      (node (ref "R38") (pin "2") (pinfunction "2_2") (pintype "passive"))
    )
    (net (code "71") (name "Net-(D18-K)") (class "Default")
      (node (ref "C37") (pin "2") (pinfunction "2_2") (pintype "passive"))
      (node (ref "D18") (pin "2") (pinfunction "K_2") (pintype "passive"))
      (node (ref "L1") (pin "1") (pinfunction "1_1") (pintype "passive"))
    )
    (net (code "72") (name "Net-(D20-A)") (class "Default")
      (node (ref "D20") (pin "1") (pinfunction "A_1") (pintype "passive"))
      (node (ref "D22") (pin "1") (pinfunction "A_1") (pintype "passive"))
    )
    (net (code "73") (name "Net-(D20-K)") (class "Default")
      (node (ref "D20") (pin "3") (pinfunction "K_3") (pintype "passive"))
      (node (ref "R41") (pin "2") (pinfunction "2_2") (pintype "passive"))
      (node (ref "R42") (pin "1") (pinfunction "1_1") (pintype "passive"))
    )
    (net (code "74") (name "Net-(D22-K)") (class "Default")
      (node (ref "C45") (pin "2") (pinfunction "2_2") (pintype "passive"))
      (node (ref "D22") (pin "3") (pinfunction "K_3") (pintype "passive"))
      (node (ref "J5") (pin "2") (pinfunction "2_2") (pintype "passive"))
      (node (ref "Q16") (pin "3") (pinfunction "C_3") (pintype "passive"))
      (node (ref "R50") (pin "1") (pinfunction "1_1") (pintype "passive"))
    )
    (net (code "75") (name "Net-(D23-A)") (class "Default")
      (node (ref "D23") (pin "1") (pinfunction "A_1") (pintype "passive"))
      (node (ref "Q14") (pin "2") (pinfunction "E_2") (pintype "passive"))
    )
    (net (code "76") (name "Net-(Q2-C)") (class "Default")
      (node (ref "Q2") (pin "3") (pinfunction "C_3") (pintype "passive"))
      (node (ref "R31") (pin "1") (pinfunction "1_1") (pintype "passive"))
    )
    (net (code "77") (name "Net-(Q3-B)") (class "Default")
      (node (ref "Q3") (pin "1") (pinfunction "B_1") (pintype "passive"))
      (node (ref "Q6") (pin "3") (pinfunction "C_3") (pintype "passive"))
      (node (ref "R36") (pin "1") (pinfunction "1_1") (pintype "passive"))
    )
    (net (code "78") (name "Net-(Q4-B)") (class "Default")
      (node (ref "Q4") (pin "1") (pinfunction "B_1") (pintype "passive"))
      (node (ref "Q5") (pin "1") (pinfunction "B_1") (pintype "passive"))
      (node (ref "Q9") (pin "3") (pinfunction "C_3") (pintype "passive"))
      (node (ref "R44") (pin "1") (pinfunction "1_1") (pintype "passive"))
    )
    (net (code "79") (name "Net-(Q4-C)") (class "Default")
      (node (ref "Q4") (pin "3") (pinfunction "C_3") (pintype "passive"))
      (node (ref "Q5") (pin "3") (pinfunction "C_3") (pintype "passive"))
    )
    (net (code "80") (name "Net-(Q7-C)") (class "Default")
      (node (ref "Q7") (pin "3") (pinfunction "C_3") (pintype "passive"))
      (node (ref "R35") (pin "2") (pinfunction "2_2") (pintype "passive"))
    )
    (net (code "81") (name "Net-(Q10-B)") (class "Default")
      (node (ref "Q10") (pin "1") (pinfunction "B_1") (pintype "passive"))
      (node (ref "R54") (pin "1") (pinfunction "1_1") (pintype "passive"))
      (node (ref "R55") (pin "2") (pinfunction "2_2") (pintype "passive"))
    )
    (net (code "82") (name "Net-(Q10-C)") (class "Default")
      (node (ref "Q10") (pin "3") (pinfunction "C_3") (pintype "passive"))
      (node (ref "R50") (pin "2") (pinfunction "2_2") (pintype "passive"))
    )
    (net (code "83") (name "Net-(Q11-C)") (class "Default")
      (node (ref "Q11") (pin "3") (pinfunction "C_3") (pintype "passive"))
      (node (ref "R51") (pin "1") (pinfunction "1_1") (pintype "passive"))
    )
    (net (code "84") (name "Net-(Q12-C)") (class "Default")
      (node (ref "Q12") (pin "3") (pinfunction "C_3") (pintype "passive"))
      (node (ref "R52") (pin "1") (pinfunction "1_1") (pintype "passive"))
    )
    (net (code "85") (name "Net-(Q13-C)") (class "Default")
      (node (ref "Q13") (pin "3") (pinfunction "C_3") (pintype "passive"))
      (node (ref "R53") (pin "1") (pinfunction "1_1") (pintype "passive"))
    )
    (net (code "86") (name "Net-(Q14-B)") (class "Default")
      (node (ref "C41") (pin "2") (pinfunction "2_2") (pintype "passive"))
      (node (ref "Q14") (pin "1") (pinfunction "B_1") (pintype "passive"))
      (node (ref "Q9") (pin "1") (pinfunction "B_1") (pintype "passive"))
      (node (ref "R43") (pin "1") (pinfunction "1_1") (pintype "passive"))
      (node (ref "U10") (pin "4") (pintype "passive"))
    )
    (net (code "87") (name "Net-(Q15-B)") (class "Default")
      (node (ref "Q15") (pin "1") (pinfunction "B_1") (pintype "passive"))
      (node (ref "Q7") (pin "1") (pinfunction "B_1") (pintype "passive"))
      (node (ref "Q8") (pin "3") (pinfunction "C_3") (pintype "passive"))
      (node (ref "R33") (pin "1") (pinfunction "1_1") (pintype "passive"))
    )
    (net (code "88") (name "Net-(Q15-C)") (class "Default")
      (node (ref "Q15") (pin "3") (pinfunction "C_3") (pintype "passive"))
      (node (ref "R55") (pin "1") (pinfunction "1_1") (pintype "passive"))
    )
    (net (code "89") (name "Net-(R45-Pad2)") (class "Default")
      (node (ref "R45") (pin "2") (pinfunction "2_2") (pintype "passive"))
      (node (ref "U10") (pin "1") (pintype "passive"))
    )
    (net (code "90") (name "Net-(R47-Pad1)") (class "Default")
      (node (ref "R47") (pin "1") (pinfunction "1_1") (pintype "passive"))
      (node (ref "R51") (pin "2") (pinfunction "2_2") (pintype "passive"))
    )
    (net (code "91") (name "Net-(R48-Pad1)") (class "Default")
      (node (ref "R48") (pin "1") (pinfunction "1_1") (pintype "passive"))
      (node (ref "R52") (pin "2") (pinfunction "2_2") (pintype "passive"))
    )
    (net (code "92") (name "Net-(R49-Pad1)") (class "Default")
      (node (ref "R49") (pin "1") (pinfunction "1_1") (pintype "passive"))
      (node (ref "R53") (pin "2") (pinfunction "2_2") (pintype "passive"))
    )
    (net (code "93") (name "Net-(U7-CREF)") (class "Default")
      (node (ref "C25") (pin "1") (pinfunction "1_1") (pintype "passive"))
      (node (ref "U7") (pin "24") (pinfunction "CREF_24") (pintype "passive"))
    )
    (net (code "94") (name "Net-(U7-VCC)") (class "Default")
      (node (ref "C27") (pin "1") (pinfunction "1_1") (pintype "passive"))
      (node (ref "U7") (pin "17") (pinfunction "VCC_17") (pintype "passive"))
    )
    (net (code "95") (name "Net-(U8-CREF)") (class "Default")
      (node (ref "C26") (pin "1") (pinfunction "1_1") (pintype "passive"))
      (node (ref "U8") (pin "24") (pinfunction "CREF_24") (pintype "passive"))
    )
    (net (code "96") (name "Net-(U8-VCC)") (class "Default")
      (node (ref "C28") (pin "1") (pinfunction "1_1") (pintype "passive"))
      (node (ref "U8") (pin "17") (pinfunction "VCC_17") (pintype "passive"))
    )
    (net (code "97") (name "Net-(U9-CB)") (class "Default")
      (node (ref "C37") (pin "1") (pinfunction "1_1") (pintype "passive"))
      (node (ref "U9") (pin "1") (pinfunction "CB_1") (pintype "passive"))
      (node (ref "U9") (pin "6") (pinfunction "SW_6") (pintype "passive"))
    )
    (net (code "98") (name "Net-(U9-FB)") (class "Default")
      (node (ref "R40") (pin "1") (pinfunction "1_1") (pintype "passive"))
      (node (ref "R46") (pin "2") (pinfunction "2_2") (pintype "passive"))
      (node (ref "U9") (pin "3") (pinfunction "FB_3") (pintype "passive"))
    )
    (net (code "99") (name "VBL") (class "Default")
      (node (ref "Q3") (pin "3") (pinfunction "C_3") (pintype "passive"))
    )
    (net (code "100") (name "VCC") (class "Default")
      (node (ref "C42") (pin "1") (pinfunction "1_1") (pintype "passive"))
      (node (ref "C43") (pin "1") (pinfunction "1_1") (pintype "passive"))
      (node (ref "D23") (pin "2") (pinfunction "K_2") (pintype "passive"))
      (node (ref "Q5") (pin "2") (pinfunction "E_2") (pintype "passive"))
      (node (ref "U9") (pin "4") (pinfunction "SHDN_4") (pintype "passive"))
      (node (ref "U9") (pin "5") (pinfunction "VIN_5") (pintype "passive"))
    )
    (net (code "101") (name "VUSB") (class "Default")
      (node (ref "C46") (pin "1") (pinfunction "1_1") (pintype "passive"))
      (node (ref "Q14") (pin "3") (pinfunction "C_3") (pintype "passive"))
      (node (ref "R38") (pin "1") (pinfunction "1_1") (pintype "passive"))
      (node (ref "R45") (pin "1") (pinfunction "1_1") (pintype "passive"))
    )
  )
)
